# io-board-b-g.net
KiCad netlist of a schematic drawn in EAGLE
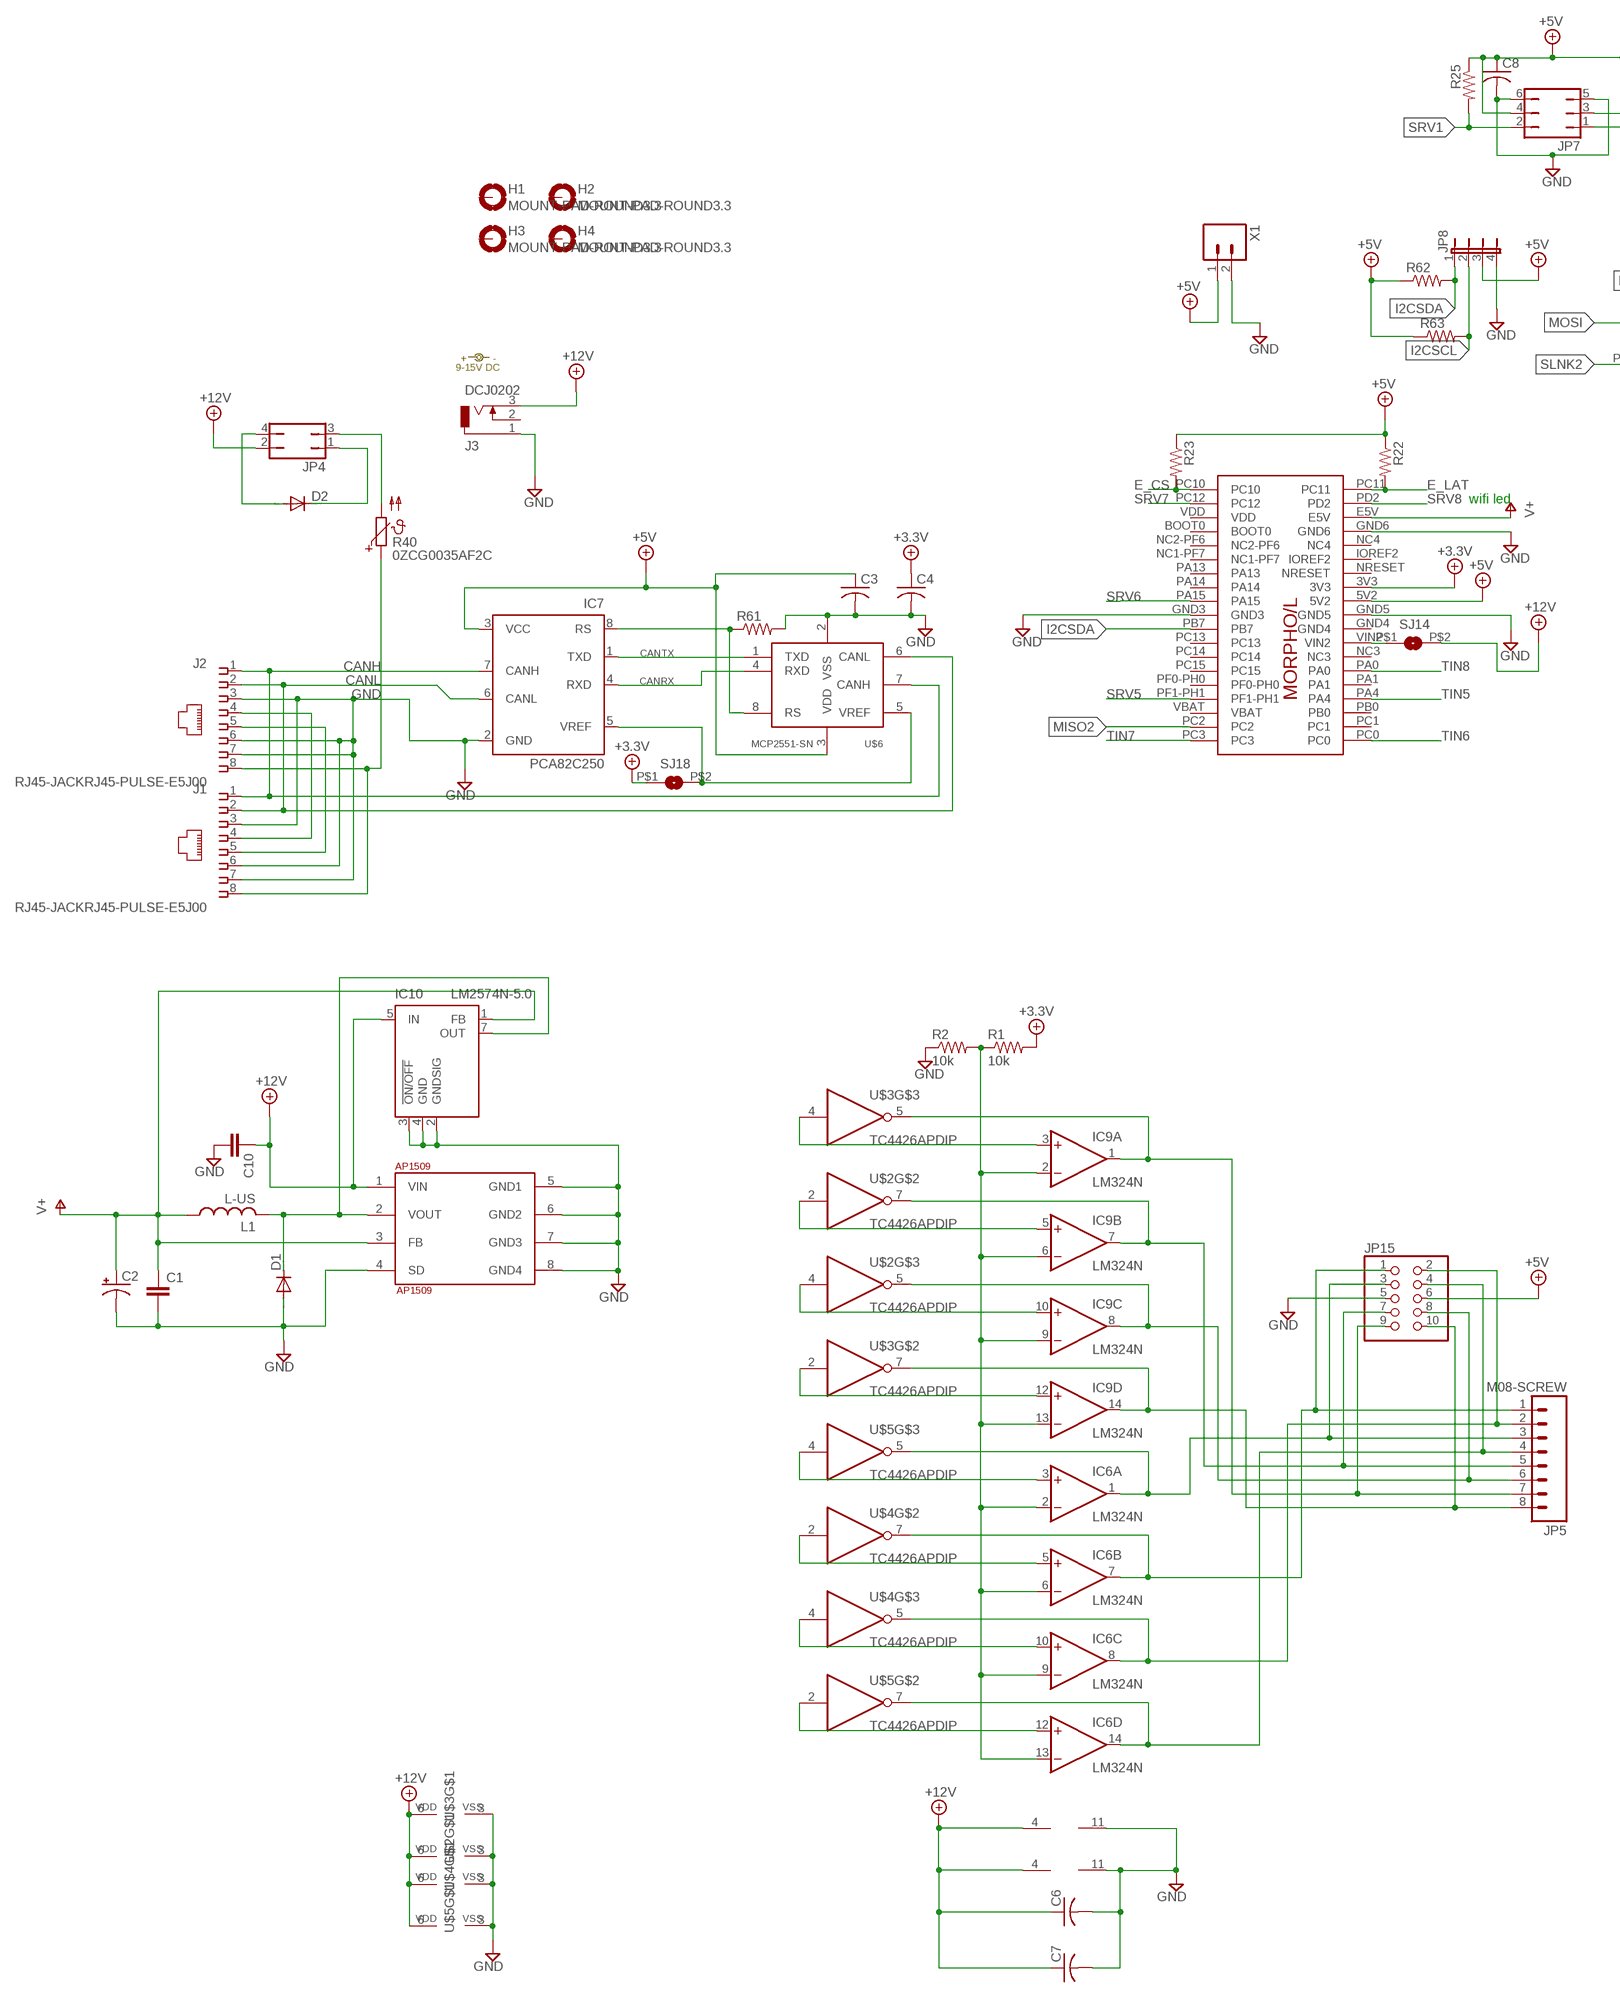
[diagram p0: schematic, sheet 1, part 1 of 2]
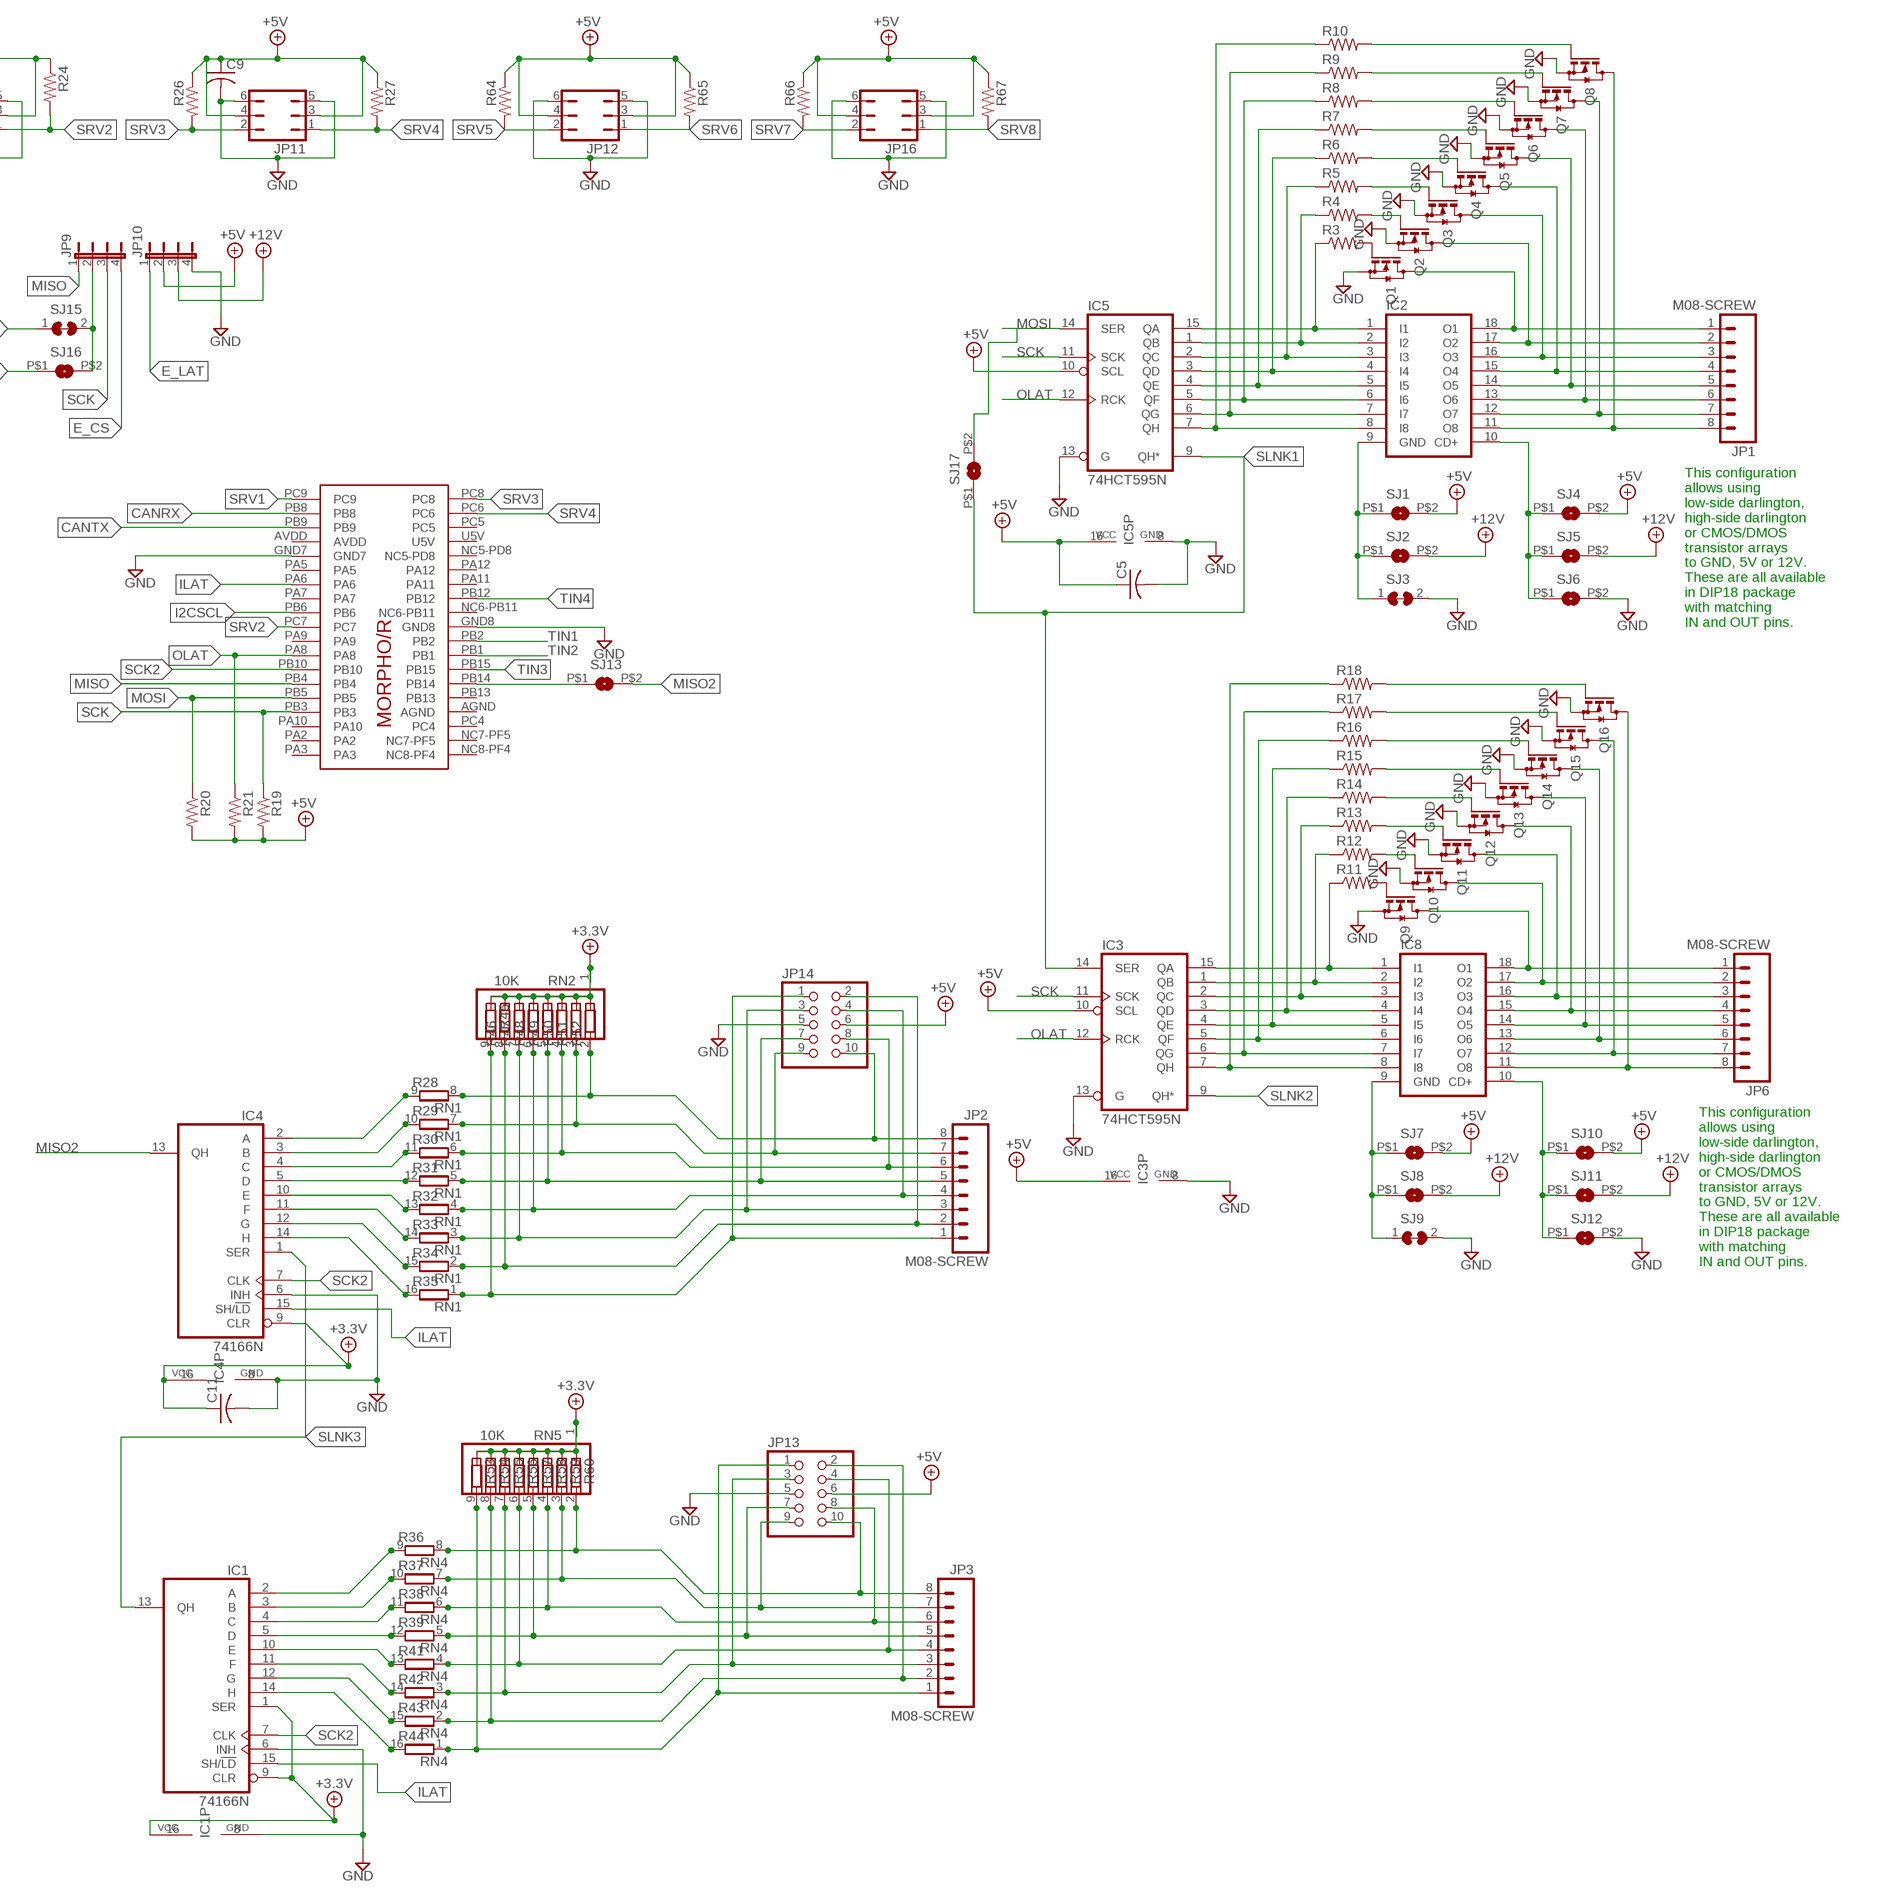
[diagram p1: schematic, sheet 1, part 2 of 2]

(export (version "E")
  (design (tool "Eeschema 10.0.6"))
  (components
    (comp (ref "+12V")
      (value "9-15V DC")
      (footprint "eagle-import:POWER_USAGE")
      (libsource (lib "eagle-import") (part "DOC-POWER_LABEL"))
    )
    (comp (ref "AP1509")
      (value "AP1509")
      (footprint "eagle-import:SO-08")
      (libsource (lib "eagle-import") (part "AP1509"))
    )
    (comp (ref "C1")
      (value "C-EUC1206")
      (footprint "eagle-import:C1206")
      (libsource (lib "eagle-import") (part "C-EUC1206"))
    )
    (comp (ref "C2")
      (value "CPOL-USE2.5-5")
      (footprint "eagle-import:E2,5-5")
      (libsource (lib "eagle-import") (part "CPOL-USE2.5-5"))
    )
    (comp (ref "C3")
      (value "C-USC0805")
      (footprint "eagle-import:C0805")
      (libsource (lib "eagle-import") (part "C-USC0805"))
    )
    (comp (ref "C4")
      (value "C-USC0805")
      (footprint "eagle-import:C0805")
      (libsource (lib "eagle-import") (part "C-USC0805"))
    )
    (comp (ref "C5")
      (value "C-USC0805")
      (footprint "eagle-import:C0805")
      (libsource (lib "eagle-import") (part "C-USC0805"))
    )
    (comp (ref "C6")
      (value "C-USC1206")
      (footprint "eagle-import:C1206")
      (libsource (lib "eagle-import") (part "C-USC1206"))
    )
    (comp (ref "C7")
      (value "C-USC1206")
      (footprint "eagle-import:C1206")
      (libsource (lib "eagle-import") (part "C-USC1206"))
    )
    (comp (ref "C8")
      (value "C-USC1206")
      (footprint "eagle-import:C1206")
      (libsource (lib "eagle-import") (part "C-USC1206"))
    )
    (comp (ref "C9")
      (value "C-USC1206")
      (footprint "eagle-import:C1206")
      (libsource (lib "eagle-import") (part "C-USC1206"))
    )
    (comp (ref "C10")
      (value "C-EUC1206")
      (footprint "eagle-import:C1206")
      (libsource (lib "eagle-import") (part "C-EUC1206"))
    )
    (comp (ref "C11")
      (value "C-USC0805")
      (footprint "eagle-import:C0805")
      (libsource (lib "eagle-import") (part "C-USC0805"))
    )
    (comp (ref "D1")
      (value "DIODE-DO41-7.6")
      (footprint "eagle-import:DO41-7.6")
      (libsource (lib "eagle-import") (part "DIODE-DO41-7.6"))
    )
    (comp (ref "D2")
      (value "DIODE-DO41-7.6")
      (footprint "eagle-import:DO41-7.6")
      (libsource (lib "eagle-import") (part "DIODE-DO41-7.6"))
    )
    (comp (ref "H1")
      (value "MOUNT-PAD-ROUND3.3")
      (footprint "eagle-import:3,3-PAD")
      (libsource (lib "eagle-import") (part "MOUNT-PAD-ROUND3.3"))
    )
    (comp (ref "H2")
      (value "MOUNT-PAD-ROUND3.3")
      (footprint "eagle-import:3,3-PAD")
      (libsource (lib "eagle-import") (part "MOUNT-PAD-ROUND3.3"))
    )
    (comp (ref "H3")
      (value "MOUNT-PAD-ROUND3.3")
      (footprint "eagle-import:3,3-PAD")
      (libsource (lib "eagle-import") (part "MOUNT-PAD-ROUND3.3"))
    )
    (comp (ref "H4")
      (value "MOUNT-PAD-ROUND3.3")
      (footprint "eagle-import:3,3-PAD")
      (libsource (lib "eagle-import") (part "MOUNT-PAD-ROUND3.3"))
    )
    (comp (ref "IC1")
      (value "74166N")
      (footprint "eagle-import:DIL16")
      (libsource (lib "eagle-import") (part "74166N"))
    )
    (comp (ref "IC2")
      (value "ULN2803A")
      (footprint "eagle-import:DIL18-THIN")
      (libsource (lib "eagle-import") (part "ULN2803A"))
    )
    (comp (ref "IC3")
      (value "74HCT595N")
      (footprint "eagle-import:DIL16")
      (libsource (lib "eagle-import") (part "74595NHCT"))
    )
    (comp (ref "IC4")
      (value "74166N")
      (footprint "eagle-import:DIL16")
      (libsource (lib "eagle-import") (part "74166N"))
    )
    (comp (ref "IC5")
      (value "74HCT595N")
      (footprint "eagle-import:DIL16")
      (libsource (lib "eagle-import") (part "74595NHCT"))
    )
    (comp (ref "IC6")
      (value "LM324N")
      (footprint "eagle-import:DIL14")
      (libsource (lib "eagle-import") (part "LM324N"))
    )
    (comp (ref "IC7")
      (value "PCA82C250")
      (footprint "eagle-import:DIL08")
      (libsource (lib "eagle-import") (part "PCA82C250"))
    )
    (comp (ref "IC8")
      (value "ULN2803A")
      (footprint "eagle-import:DIL18-THIN")
      (libsource (lib "eagle-import") (part "ULN2803A"))
    )
    (comp (ref "IC9")
      (value "LM324N")
      (footprint "eagle-import:DIL14")
      (libsource (lib "eagle-import") (part "LM324N"))
    )
    (comp (ref "IC10")
      (value "LM2574N-5.0")
      (footprint "eagle-import:DIL08")
      (libsource (lib "eagle-import") (part "LM2574?-N5.0"))
    )
    (comp (ref "J1")
      (value "RJ45-JACKRJ45-PULSE-E5J00")
      (footprint "eagle-import:RJ45-PULSE-E5J88")
      (libsource (lib "eagle-import") (part "RJ45-JACKRJ45-PULSE-E5J00"))
    )
    (comp (ref "J2")
      (value "RJ45-JACKRJ45-PULSE-E5J00")
      (footprint "eagle-import:RJ45-PULSE-E5J88")
      (libsource (lib "eagle-import") (part "RJ45-JACKRJ45-PULSE-E5J00"))
    )
    (comp (ref "J3")
      (value "DCJ0202")
      (footprint "eagle-import:DCJ0202")
      (libsource (lib "eagle-import") (part "DCJ0202"))
    )
    (comp (ref "JP1")
      (value "M08-SCREW")
      (footprint "eagle-import:1X08_TERMINAL")
      (libsource (lib "eagle-import") (part "M08-SCREW"))
    )
    (comp (ref "JP2")
      (value "M08-SCREW")
      (footprint "eagle-import:1X08_TERMINAL")
      (libsource (lib "eagle-import") (part "M08-SCREW"))
    )
    (comp (ref "JP3")
      (value "M08-SCREW")
      (footprint "eagle-import:1X08_TERMINAL")
      (libsource (lib "eagle-import") (part "M08-SCREW"))
    )
    (comp (ref "JP4")
      (value "JP2Q")
      (footprint "eagle-import:JP2Q")
      (libsource (lib "eagle-import") (part "JP2Q"))
    )
    (comp (ref "JP5")
      (value "M08-SCREW")
      (footprint "eagle-import:1X08_TERMINAL")
      (libsource (lib "eagle-import") (part "M08-SCREW"))
    )
    (comp (ref "JP6")
      (value "M08-SCREW")
      (footprint "eagle-import:1X08_TERMINAL")
      (libsource (lib "eagle-import") (part "M08-SCREW"))
    )
    (comp (ref "JP7")
      (value "JP3Q")
      (footprint "eagle-import:JP3Q")
      (libsource (lib "eagle-import") (part "JP3Q"))
    )
    (comp (ref "JP8")
      (value "JP4-FLAT")
      (footprint "eagle-import:JP4F")
      (libsource (lib "eagle-import") (part "JP4-FLAT"))
    )
    (comp (ref "JP9")
      (value "JP4-FLAT")
      (footprint "eagle-import:JP4F")
      (libsource (lib "eagle-import") (part "JP4-FLAT"))
    )
    (comp (ref "JP10")
      (value "JP4-FLAT")
      (footprint "eagle-import:JP4F")
      (libsource (lib "eagle-import") (part "JP4-FLAT"))
    )
    (comp (ref "JP11")
      (value "JP3Q")
      (footprint "eagle-import:JP3Q")
      (libsource (lib "eagle-import") (part "JP3Q"))
    )
    (comp (ref "JP12")
      (value "JP3Q")
      (footprint "eagle-import:JP3Q")
      (libsource (lib "eagle-import") (part "JP3Q"))
    )
    (comp (ref "JP13")
      (value "PINHD-2X5CN")
      (footprint "eagle-import:CON10M")
      (libsource (lib "eagle-import") (part "PINHD-2X5CN"))
    )
    (comp (ref "JP14")
      (value "PINHD-2X5CN")
      (footprint "eagle-import:CON10M")
      (libsource (lib "eagle-import") (part "PINHD-2X5CN"))
    )
    (comp (ref "JP15")
      (value "PINHD-2X5CN")
      (footprint "eagle-import:CON10M")
      (libsource (lib "eagle-import") (part "PINHD-2X5CN"))
    )
    (comp (ref "JP16")
      (value "JP3Q")
      (footprint "eagle-import:JP3Q")
      (libsource (lib "eagle-import") (part "JP3Q"))
    )
    (comp (ref "L1")
      (value "L-US")
      (footprint "eagle-import:L5-8,5")
      (libsource (lib "eagle-import") (part "L-US"))
    )
    (comp (ref "Q1")
      (value "BSS123")
      (footprint "eagle-import:SOT23")
      (libsource (lib "eagle-import") (part "BSS123"))
    )
    (comp (ref "Q2")
      (value "BSS123")
      (footprint "eagle-import:SOT23")
      (libsource (lib "eagle-import") (part "BSS123"))
    )
    (comp (ref "Q3")
      (value "BSS123")
      (footprint "eagle-import:SOT23")
      (libsource (lib "eagle-import") (part "BSS123"))
    )
    (comp (ref "Q4")
      (value "BSS123")
      (footprint "eagle-import:SOT23")
      (libsource (lib "eagle-import") (part "BSS123"))
    )
    (comp (ref "Q5")
      (value "BSS123")
      (footprint "eagle-import:SOT23")
      (libsource (lib "eagle-import") (part "BSS123"))
    )
    (comp (ref "Q6")
      (value "BSS123")
      (footprint "eagle-import:SOT23")
      (libsource (lib "eagle-import") (part "BSS123"))
    )
    (comp (ref "Q7")
      (value "BSS123")
      (footprint "eagle-import:SOT23")
      (libsource (lib "eagle-import") (part "BSS123"))
    )
    (comp (ref "Q8")
      (value "BSS123")
      (footprint "eagle-import:SOT23")
      (libsource (lib "eagle-import") (part "BSS123"))
    )
    (comp (ref "Q9")
      (value "BSS123")
      (footprint "eagle-import:SOT23")
      (libsource (lib "eagle-import") (part "BSS123"))
    )
    (comp (ref "Q10")
      (value "BSS123")
      (footprint "eagle-import:SOT23")
      (libsource (lib "eagle-import") (part "BSS123"))
    )
    (comp (ref "Q11")
      (value "BSS123")
      (footprint "eagle-import:SOT23")
      (libsource (lib "eagle-import") (part "BSS123"))
    )
    (comp (ref "Q12")
      (value "BSS123")
      (footprint "eagle-import:SOT23")
      (libsource (lib "eagle-import") (part "BSS123"))
    )
    (comp (ref "Q13")
      (value "BSS123")
      (footprint "eagle-import:SOT23")
      (libsource (lib "eagle-import") (part "BSS123"))
    )
    (comp (ref "Q14")
      (value "BSS123")
      (footprint "eagle-import:SOT23")
      (libsource (lib "eagle-import") (part "BSS123"))
    )
    (comp (ref "Q15")
      (value "BSS123")
      (footprint "eagle-import:SOT23")
      (libsource (lib "eagle-import") (part "BSS123"))
    )
    (comp (ref "Q16")
      (value "BSS123")
      (footprint "eagle-import:SOT23")
      (libsource (lib "eagle-import") (part "BSS123"))
    )
    (comp (ref "R1")
      (value "10k")
      (footprint "eagle-import:R0805")
      (libsource (lib "eagle-import") (part "R-US_R0805"))
    )
    (comp (ref "R2")
      (value "10k")
      (footprint "eagle-import:R0805")
      (libsource (lib "eagle-import") (part "R-US_R0805"))
    )
    (comp (ref "R3")
      (value "R-US_R0603")
      (footprint "eagle-import:R0603")
      (libsource (lib "eagle-import") (part "R-US_R0603"))
    )
    (comp (ref "R4")
      (value "R-US_R0603")
      (footprint "eagle-import:R0603")
      (libsource (lib "eagle-import") (part "R-US_R0603"))
    )
    (comp (ref "R5")
      (value "R-US_R0603")
      (footprint "eagle-import:R0603")
      (libsource (lib "eagle-import") (part "R-US_R0603"))
    )
    (comp (ref "R6")
      (value "R-US_R0603")
      (footprint "eagle-import:R0603")
      (libsource (lib "eagle-import") (part "R-US_R0603"))
    )
    (comp (ref "R7")
      (value "R-US_R0603")
      (footprint "eagle-import:R0603")
      (libsource (lib "eagle-import") (part "R-US_R0603"))
    )
    (comp (ref "R8")
      (value "R-US_R0603")
      (footprint "eagle-import:R0603")
      (libsource (lib "eagle-import") (part "R-US_R0603"))
    )
    (comp (ref "R9")
      (value "R-US_R0603")
      (footprint "eagle-import:R0603")
      (libsource (lib "eagle-import") (part "R-US_R0603"))
    )
    (comp (ref "R10")
      (value "R-US_R0603")
      (footprint "eagle-import:R0603")
      (libsource (lib "eagle-import") (part "R-US_R0603"))
    )
    (comp (ref "R11")
      (value "R-US_R0603")
      (footprint "eagle-import:R0603")
      (libsource (lib "eagle-import") (part "R-US_R0603"))
    )
    (comp (ref "R12")
      (value "R-US_R0603")
      (footprint "eagle-import:R0603")
      (libsource (lib "eagle-import") (part "R-US_R0603"))
    )
    (comp (ref "R13")
      (value "R-US_R0603")
      (footprint "eagle-import:R0603")
      (libsource (lib "eagle-import") (part "R-US_R0603"))
    )
    (comp (ref "R14")
      (value "R-US_R0603")
      (footprint "eagle-import:R0603")
      (libsource (lib "eagle-import") (part "R-US_R0603"))
    )
    (comp (ref "R15")
      (value "R-US_R0603")
      (footprint "eagle-import:R0603")
      (libsource (lib "eagle-import") (part "R-US_R0603"))
    )
    (comp (ref "R16")
      (value "R-US_R0603")
      (footprint "eagle-import:R0603")
      (libsource (lib "eagle-import") (part "R-US_R0603"))
    )
    (comp (ref "R17")
      (value "R-US_R0603")
      (footprint "eagle-import:R0603")
      (libsource (lib "eagle-import") (part "R-US_R0603"))
    )
    (comp (ref "R18")
      (value "R-US_R0603")
      (footprint "eagle-import:R0603")
      (libsource (lib "eagle-import") (part "R-US_R0603"))
    )
    (comp (ref "R19")
      (value "R-US_R0805")
      (footprint "eagle-import:R0805")
      (libsource (lib "eagle-import") (part "rcl_334_R-US_R0805"))
    )
    (comp (ref "R20")
      (value "R-US_R0805")
      (footprint "eagle-import:R0805")
      (libsource (lib "eagle-import") (part "rcl_334_R-US_R0805"))
    )
    (comp (ref "R21")
      (value "R-US_R0805")
      (footprint "eagle-import:R0805")
      (libsource (lib "eagle-import") (part "rcl_334_R-US_R0805"))
    )
    (comp (ref "R22")
      (value "R-US_R0805")
      (footprint "eagle-import:R0805")
      (libsource (lib "eagle-import") (part "rcl_334_R-US_R0805"))
    )
    (comp (ref "R23")
      (value "R-US_R0805")
      (footprint "eagle-import:R0805")
      (libsource (lib "eagle-import") (part "rcl_334_R-US_R0805"))
    )
    (comp (ref "R24")
      (value "R-US_R0805")
      (footprint "eagle-import:R0805")
      (libsource (lib "eagle-import") (part "rcl_334_R-US_R0805"))
    )
    (comp (ref "R25")
      (value "R-US_R0805")
      (footprint "eagle-import:R0805")
      (libsource (lib "eagle-import") (part "rcl_334_R-US_R0805"))
    )
    (comp (ref "R26")
      (value "R-US_R0805")
      (footprint "eagle-import:R0805")
      (libsource (lib "eagle-import") (part "rcl_334_R-US_R0805"))
    )
    (comp (ref "R27")
      (value "R-US_R0805")
      (footprint "eagle-import:R0805")
      (libsource (lib "eagle-import") (part "rcl_334_R-US_R0805"))
    )
    (comp (ref "R28")
      (value "R-EU_R0603")
      (footprint "eagle-import:R0603")
      (libsource (lib "eagle-import") (part "R-EU_R0603"))
    )
    (comp (ref "R29")
      (value "R-EU_R0603")
      (footprint "eagle-import:R0603")
      (libsource (lib "eagle-import") (part "R-EU_R0603"))
    )
    (comp (ref "R30")
      (value "R-EU_R0603")
      (footprint "eagle-import:R0603")
      (libsource (lib "eagle-import") (part "R-EU_R0603"))
    )
    (comp (ref "R31")
      (value "R-EU_R0603")
      (footprint "eagle-import:R0603")
      (libsource (lib "eagle-import") (part "R-EU_R0603"))
    )
    (comp (ref "R32")
      (value "R-EU_R0603")
      (footprint "eagle-import:R0603")
      (libsource (lib "eagle-import") (part "R-EU_R0603"))
    )
    (comp (ref "R33")
      (value "R-EU_R0603")
      (footprint "eagle-import:R0603")
      (libsource (lib "eagle-import") (part "R-EU_R0603"))
    )
    (comp (ref "R34")
      (value "R-EU_R0603")
      (footprint "eagle-import:R0603")
      (libsource (lib "eagle-import") (part "R-EU_R0603"))
    )
    (comp (ref "R35")
      (value "R-EU_R0603")
      (footprint "eagle-import:R0603")
      (libsource (lib "eagle-import") (part "R-EU_R0603"))
    )
    (comp (ref "R36")
      (value "R-EU_R0603")
      (footprint "eagle-import:R0603")
      (libsource (lib "eagle-import") (part "R-EU_R0603"))
    )
    (comp (ref "R37")
      (value "R-EU_R0603")
      (footprint "eagle-import:R0603")
      (libsource (lib "eagle-import") (part "R-EU_R0603"))
    )
    (comp (ref "R38")
      (value "R-EU_R0603")
      (footprint "eagle-import:R0603")
      (libsource (lib "eagle-import") (part "R-EU_R0603"))
    )
    (comp (ref "R39")
      (value "R-EU_R0603")
      (footprint "eagle-import:R0603")
      (libsource (lib "eagle-import") (part "R-EU_R0603"))
    )
    (comp (ref "R40")
      (value "0ZCG0035AF2C")
      (footprint "eagle-import:PTC1812")
      (libsource (lib "eagle-import") (part "PTC_1812"))
    )
    (comp (ref "R41")
      (value "R-EU_R0603")
      (footprint "eagle-import:R0603")
      (libsource (lib "eagle-import") (part "R-EU_R0603"))
    )
    (comp (ref "R42")
      (value "R-EU_R0603")
      (footprint "eagle-import:R0603")
      (libsource (lib "eagle-import") (part "R-EU_R0603"))
    )
    (comp (ref "R43")
      (value "R-EU_R0603")
      (footprint "eagle-import:R0603")
      (libsource (lib "eagle-import") (part "R-EU_R0603"))
    )
    (comp (ref "R44")
      (value "R-EU_R0603")
      (footprint "eagle-import:R0603")
      (libsource (lib "eagle-import") (part "R-EU_R0603"))
    )
    (comp (ref "R45")
      (value "R-EU_R0603")
      (footprint "eagle-import:R0603")
      (libsource (lib "eagle-import") (part "R-EU_R0603"))
    )
    (comp (ref "R46")
      (value "R-EU_R0603")
      (footprint "eagle-import:R0603")
      (libsource (lib "eagle-import") (part "R-EU_R0603"))
    )
    (comp (ref "R47")
      (value "R-EU_R0603")
      (footprint "eagle-import:R0603")
      (libsource (lib "eagle-import") (part "R-EU_R0603"))
    )
    (comp (ref "R48")
      (value "R-EU_R0603")
      (footprint "eagle-import:R0603")
      (libsource (lib "eagle-import") (part "R-EU_R0603"))
    )
    (comp (ref "R49")
      (value "R-EU_R0603")
      (footprint "eagle-import:R0603")
      (libsource (lib "eagle-import") (part "R-EU_R0603"))
    )
    (comp (ref "R50")
      (value "R-EU_R0603")
      (footprint "eagle-import:R0603")
      (libsource (lib "eagle-import") (part "R-EU_R0603"))
    )
    (comp (ref "R51")
      (value "R-EU_R0603")
      (footprint "eagle-import:R0603")
      (libsource (lib "eagle-import") (part "R-EU_R0603"))
    )
    (comp (ref "R52")
      (value "R-EU_R0603")
      (footprint "eagle-import:R0603")
      (libsource (lib "eagle-import") (part "R-EU_R0603"))
    )
    (comp (ref "R53")
      (value "R-EU_R0603")
      (footprint "eagle-import:R0603")
      (libsource (lib "eagle-import") (part "R-EU_R0603"))
    )
    (comp (ref "R54")
      (value "R-EU_R0603")
      (footprint "eagle-import:R0603")
      (libsource (lib "eagle-import") (part "R-EU_R0603"))
    )
    (comp (ref "R55")
      (value "R-EU_R0603")
      (footprint "eagle-import:R0603")
      (libsource (lib "eagle-import") (part "R-EU_R0603"))
    )
    (comp (ref "R56")
      (value "R-EU_R0603")
      (footprint "eagle-import:R0603")
      (libsource (lib "eagle-import") (part "R-EU_R0603"))
    )
    (comp (ref "R57")
      (value "R-EU_R0603")
      (footprint "eagle-import:R0603")
      (libsource (lib "eagle-import") (part "R-EU_R0603"))
    )
    (comp (ref "R58")
      (value "R-EU_R0603")
      (footprint "eagle-import:R0603")
      (libsource (lib "eagle-import") (part "R-EU_R0603"))
    )
    (comp (ref "R59")
      (value "R-EU_R0603")
      (footprint "eagle-import:R0603")
      (libsource (lib "eagle-import") (part "R-EU_R0603"))
    )
    (comp (ref "R60")
      (value "R-EU_R0603")
      (footprint "eagle-import:R0603")
      (libsource (lib "eagle-import") (part "R-EU_R0603"))
    )
    (comp (ref "R61")
      (value "R-US_R0805")
      (footprint "eagle-import:R0805")
      (libsource (lib "eagle-import") (part "rcl_334_R-US_R0805"))
    )
    (comp (ref "R62")
      (value "R-US_R0805")
      (footprint "eagle-import:R0805")
      (libsource (lib "eagle-import") (part "rcl_334_R-US_R0805"))
    )
    (comp (ref "R63")
      (value "R-US_R0805")
      (footprint "eagle-import:R0805")
      (libsource (lib "eagle-import") (part "rcl_334_R-US_R0805"))
    )
    (comp (ref "R64")
      (value "R-US_R0805")
      (footprint "eagle-import:R0805")
      (libsource (lib "eagle-import") (part "rcl_334_R-US_R0805"))
    )
    (comp (ref "R65")
      (value "R-US_R0805")
      (footprint "eagle-import:R0805")
      (libsource (lib "eagle-import") (part "rcl_334_R-US_R0805"))
    )
    (comp (ref "R66")
      (value "R-US_R0805")
      (footprint "eagle-import:R0805")
      (libsource (lib "eagle-import") (part "rcl_334_R-US_R0805"))
    )
    (comp (ref "R67")
      (value "R-US_R0805")
      (footprint "eagle-import:R0805")
      (libsource (lib "eagle-import") (part "rcl_334_R-US_R0805"))
    )
    (comp (ref "RN1")
      (value "8R-P")
      (footprint "eagle-import:DIL16")
      (libsource (lib "eagle-import") (part "8R-P"))
    )
    (comp (ref "RN2")
      (value "10K")
      (footprint "eagle-import:SIL9")
      (libsource (lib "eagle-import") (part "G08R"))
    )
    (comp (ref "RN4")
      (value "8R-P")
      (footprint "eagle-import:DIL16")
      (libsource (lib "eagle-import") (part "8R-P"))
    )
    (comp (ref "RN5")
      (value "10K")
      (footprint "eagle-import:SIL9")
      (libsource (lib "eagle-import") (part "G08R"))
    )
    (comp (ref "SJ1")
      (value "SJRND2")
      (footprint "eagle-import:SJ_RND2")
      (libsource (lib "eagle-import") (part "SJRND2"))
    )
    (comp (ref "SJ2")
      (value "SJRND2")
      (footprint "eagle-import:SJ_RND2")
      (libsource (lib "eagle-import") (part "SJRND2"))
    )
    (comp (ref "SJ3")
      (value "SJ-C")
      (footprint "eagle-import:SJW-C")
      (libsource (lib "eagle-import") (part "SJ-C"))
    )
    (comp (ref "SJ4")
      (value "SJRND2")
      (footprint "eagle-import:SJ_RND2")
      (libsource (lib "eagle-import") (part "SJRND2"))
    )
    (comp (ref "SJ5")
      (value "SJRND2")
      (footprint "eagle-import:SJ_RND2")
      (libsource (lib "eagle-import") (part "SJRND2"))
    )
    (comp (ref "SJ6")
      (value "SJRND2")
      (footprint "eagle-import:SJ_RND2")
      (libsource (lib "eagle-import") (part "SJRND2"))
    )
    (comp (ref "SJ7")
      (value "SJRND2")
      (footprint "eagle-import:SJ_RND2")
      (libsource (lib "eagle-import") (part "SJRND2"))
    )
    (comp (ref "SJ8")
      (value "SJRND2")
      (footprint "eagle-import:SJ_RND2")
      (libsource (lib "eagle-import") (part "SJRND2"))
    )
    (comp (ref "SJ9")
      (value "SJ-C")
      (footprint "eagle-import:SJW-C")
      (libsource (lib "eagle-import") (part "SJ-C"))
    )
    (comp (ref "SJ10")
      (value "SJRND2")
      (footprint "eagle-import:SJ_RND2")
      (libsource (lib "eagle-import") (part "SJRND2"))
    )
    (comp (ref "SJ11")
      (value "SJRND2")
      (footprint "eagle-import:SJ_RND2")
      (libsource (lib "eagle-import") (part "SJRND2"))
    )
    (comp (ref "SJ12")
      (value "SJRND2")
      (footprint "eagle-import:SJ_RND2")
      (libsource (lib "eagle-import") (part "SJRND2"))
    )
    (comp (ref "SJ13")
      (value "SJRND2")
      (footprint "eagle-import:SJ_RND2")
      (libsource (lib "eagle-import") (part "SJRND2"))
    )
    (comp (ref "SJ14")
      (value "SJRND2")
      (footprint "eagle-import:SJ_RND2")
      (libsource (lib "eagle-import") (part "SJRND2"))
    )
    (comp (ref "SJ15")
      (value "SJ-C")
      (footprint "eagle-import:SJW-C")
      (libsource (lib "eagle-import") (part "SJ-C"))
    )
    (comp (ref "SJ16")
      (value "SJRND2")
      (footprint "eagle-import:SJ_RND2")
      (libsource (lib "eagle-import") (part "SJRND2"))
    )
    (comp (ref "SJ17")
      (value "SJRND2")
      (footprint "eagle-import:SJ_RND2")
      (libsource (lib "eagle-import") (part "SJRND2"))
    )
    (comp (ref "SJ18")
      (value "SJRND2")
      (footprint "eagle-import:SJ_RND2")
      (libsource (lib "eagle-import") (part "SJRND2"))
    )
    (comp (ref "U$1")
      (value "NUCLEO_64_GENERIC")
      (footprint "eagle-import:NUCLEO_BRD_BASE64")
      (libsource (lib "eagle-import") (part "NUCLEO_64_GENERIC"))
    )
    (comp (ref "U$2")
      (value "TC4426APDIP")
      (footprint "eagle-import:DIL08-LONG")
      (libsource (lib "eagle-import") (part "TC4426APDIP"))
    )
    (comp (ref "U$3")
      (value "TC4426APDIP")
      (footprint "eagle-import:DIL08-LONG")
      (libsource (lib "eagle-import") (part "TC4426APDIP"))
    )
    (comp (ref "U$4")
      (value "TC4426APDIP")
      (footprint "eagle-import:DIL08-LONG")
      (libsource (lib "eagle-import") (part "TC4426APDIP"))
    )
    (comp (ref "U$5")
      (value "TC4426APDIP")
      (footprint "eagle-import:DIL08-LONG")
      (libsource (lib "eagle-import") (part "TC4426APDIP"))
    )
    (comp (ref "U$6")
      (value "MCP2551-SN")
      (footprint "eagle-import:SO-08")
      (libsource (lib "eagle-import") (part "MCP2551-SN"))
    )
    (comp (ref "X1")
      (value "CONNECTOR-M023.5MM-LOCK")
      (footprint "eagle-import:SCREWTERMINAL-3.5MM-2_LOCK")
      (libsource (lib "eagle-import") (part "CONNECTOR-M023.5MM-LOCK"))
    )
  )
  (nets
    (net (code "1") (name "+3.3V") (class "Default")
      (node (ref "C11") (pin "1") (pinfunction "1_1") (pintype "passive"))
      (node (ref "C4") (pin "1") (pinfunction "1_1") (pintype "passive"))
      (node (ref "IC1") (pin "1") (pinfunction "SER_1") (pintype "input"))
      (node (ref "IC1") (pin "16") (pinfunction "VCC_16") (pintype "power_in"))
      (node (ref "IC1") (pin "9") (pinfunction "CLR_9") (pintype "input"))
      (node (ref "IC4") (pin "16") (pinfunction "VCC_16") (pintype "power_in"))
      (node (ref "IC4") (pin "9") (pinfunction "CLR_9") (pintype "input"))
      (node (ref "R1") (pin "2") (pinfunction "2_2") (pintype "passive"))
      (node (ref "R45") (pin "1") (pinfunction "1_1") (pintype "passive"))
      (node (ref "R46") (pin "2") (pinfunction "2_2") (pintype "passive"))
      (node (ref "R47") (pin "2") (pinfunction "2_2") (pintype "passive"))
      (node (ref "R48") (pin "2") (pinfunction "2_2") (pintype "passive"))
      (node (ref "R49") (pin "2") (pinfunction "2_2") (pintype "passive"))
      (node (ref "R50") (pin "2") (pinfunction "2_2") (pintype "passive"))
      (node (ref "R51") (pin "2") (pinfunction "2_2") (pintype "passive"))
      (node (ref "R52") (pin "2") (pinfunction "2_2") (pintype "passive"))
      (node (ref "R53") (pin "1") (pinfunction "1_1") (pintype "passive"))
      (node (ref "R54") (pin "1") (pinfunction "1_1") (pintype "passive"))
      (node (ref "R55") (pin "1") (pinfunction "1_1") (pintype "passive"))
      (node (ref "R56") (pin "1") (pinfunction "1_1") (pintype "passive"))
      (node (ref "R57") (pin "1") (pinfunction "1_1") (pintype "passive"))
      (node (ref "R58") (pin "1") (pinfunction "1_1") (pintype "passive"))
      (node (ref "R59") (pin "1") (pinfunction "1_1") (pintype "passive"))
      (node (ref "R60") (pin "1") (pinfunction "1_1") (pintype "passive"))
      (node (ref "RN2") (pin "1") (pinfunction "1_1") (pintype "passive"))
      (node (ref "RN5") (pin "1") (pinfunction "1_1") (pintype "passive"))
      (node (ref "SJ18") (pin "P$1") (pinfunction "1_P$1") (pintype "passive"))
      (node (ref "U$1") (pin "3V3") (pinfunction "3V3_3V3") (pintype "power_in"))
    )
    (net (code "2") (name "+5V") (class "Default")
      (node (ref "C3") (pin "1") (pinfunction "1_1") (pintype "passive"))
      (node (ref "C5") (pin "1") (pinfunction "1_1") (pintype "passive"))
      (node (ref "C8") (pin "1") (pinfunction "1_1") (pintype "passive"))
      (node (ref "C9") (pin "1") (pinfunction "1_1") (pintype "passive"))
      (node (ref "IC3") (pin "10") (pinfunction "SCL_10") (pintype "input"))
      (node (ref "IC3") (pin "16") (pinfunction "VCC_16") (pintype "power_in"))
      (node (ref "IC5") (pin "10") (pinfunction "SCL_10") (pintype "input"))
      (node (ref "IC5") (pin "16") (pinfunction "VCC_16") (pintype "power_in"))
      (node (ref "IC7") (pin "3") (pinfunction "VCC_3") (pintype "power_in"))
      (node (ref "JP10") (pin "2") (pinfunction "2_2") (pintype "passive"))
      (node (ref "JP11") (pin "3") (pinfunction "3_3") (pintype "passive"))
      (node (ref "JP11") (pin "4") (pinfunction "4_4") (pintype "passive"))
      (node (ref "JP12") (pin "3") (pinfunction "3_3") (pintype "passive"))
      (node (ref "JP12") (pin "4") (pinfunction "4_4") (pintype "passive"))
      (node (ref "JP13") (pin "6") (pinfunction "6_6") (pintype "passive"))
      (node (ref "JP14") (pin "6") (pinfunction "6_6") (pintype "passive"))
      (node (ref "JP15") (pin "6") (pinfunction "6_6") (pintype "passive"))
      (node (ref "JP16") (pin "3") (pinfunction "3_3") (pintype "passive"))
      (node (ref "JP16") (pin "4") (pinfunction "4_4") (pintype "passive"))
      (node (ref "JP7") (pin "3") (pinfunction "3_3") (pintype "passive"))
      (node (ref "JP7") (pin "4") (pinfunction "4_4") (pintype "passive"))
      (node (ref "JP8") (pin "3") (pinfunction "3_3") (pintype "passive"))
      (node (ref "R19") (pin "2") (pinfunction "2_2") (pintype "passive"))
      (node (ref "R20") (pin "2") (pinfunction "2_2") (pintype "passive"))
      (node (ref "R21") (pin "2") (pinfunction "2_2") (pintype "passive"))
      (node (ref "R22") (pin "1") (pinfunction "1_1") (pintype "passive"))
      (node (ref "R23") (pin "1") (pinfunction "1_1") (pintype "passive"))
      (node (ref "R24") (pin "1") (pinfunction "1_1") (pintype "passive"))
      (node (ref "R25") (pin "1") (pinfunction "1_1") (pintype "passive"))
      (node (ref "R26") (pin "1") (pinfunction "1_1") (pintype "passive"))
      (node (ref "R27") (pin "1") (pinfunction "1_1") (pintype "passive"))
      (node (ref "R62") (pin "1") (pinfunction "1_1") (pintype "passive"))
      (node (ref "R63") (pin "1") (pinfunction "1_1") (pintype "passive"))
      (node (ref "R64") (pin "1") (pinfunction "1_1") (pintype "passive"))
      (node (ref "R65") (pin "1") (pinfunction "1_1") (pintype "passive"))
      (node (ref "R66") (pin "1") (pinfunction "1_1") (pintype "passive"))
      (node (ref "R67") (pin "1") (pinfunction "1_1") (pintype "passive"))
      (node (ref "SJ1") (pin "P$2") (pinfunction "2_P$2") (pintype "passive"))
      (node (ref "SJ10") (pin "P$2") (pinfunction "2_P$2") (pintype "passive"))
      (node (ref "SJ4") (pin "P$2") (pinfunction "2_P$2") (pintype "passive"))
      (node (ref "SJ7") (pin "P$2") (pinfunction "2_P$2") (pintype "passive"))
      (node (ref "U$1") (pin "5V2") (pinfunction "5V2_5V2") (pintype "power_in"))
      (node (ref "U$6") (pin "3") (pinfunction "VDD_3") (pintype "power_in"))
      (node (ref "X1") (pin "1") (pinfunction "1_1") (pintype "passive"))
    )
    (net (code "3") (name "+12V") (class "Default")
      (node (ref "AP1509") (pin "1") (pinfunction "VIN_1") (pintype "bidirectional"))
      (node (ref "C10") (pin "1") (pinfunction "1_1") (pintype "passive"))
      (node (ref "C6") (pin "1") (pinfunction "1_1") (pintype "passive"))
      (node (ref "C7") (pin "1") (pinfunction "1_1") (pintype "passive"))
      (node (ref "IC10") (pin "5") (pinfunction "IN_5") (pintype "input"))
      (node (ref "IC6") (pin "4") (pinfunction "V+_4") (pintype "power_in"))
      (node (ref "IC9") (pin "4") (pinfunction "V+_4") (pintype "power_in"))
      (node (ref "J3") (pin "3") (pinfunction "3_3") (pintype "passive"))
      (node (ref "JP10") (pin "3") (pinfunction "3_3") (pintype "passive"))
      (node (ref "JP4") (pin "2") (pinfunction "2_2") (pintype "passive"))
      (node (ref "SJ11") (pin "P$2") (pinfunction "2_P$2") (pintype "passive"))
      (node (ref "SJ14") (pin "P$2") (pinfunction "2_P$2") (pintype "passive"))
      (node (ref "SJ2") (pin "P$2") (pinfunction "2_P$2") (pintype "passive"))
      (node (ref "SJ5") (pin "P$2") (pinfunction "2_P$2") (pintype "passive"))
      (node (ref "SJ8") (pin "P$2") (pinfunction "2_P$2") (pintype "passive"))
      (node (ref "U$2") (pin "6") (pinfunction "VDD_6") (pintype "power_in"))
      (node (ref "U$3") (pin "6") (pinfunction "VDD_6") (pintype "power_in"))
      (node (ref "U$4") (pin "6") (pinfunction "VDD_6") (pintype "power_in"))
      (node (ref "U$5") (pin "6") (pinfunction "VDD_6") (pintype "power_in"))
    )
    (net (code "4") (name "/AGND") (class "Default")
      (node (ref "U$1") (pin "AGND") (pinfunction "AGND_AGND") (pintype "power_in"))
    )
    (net (code "5") (name "/AVDD") (class "Default")
      (node (ref "U$1") (pin "AVDD") (pinfunction "AVDD_AVDD") (pintype "power_in"))
    )
    (net (code "6") (name "/CANH") (class "Default")
      (node (ref "IC7") (pin "7") (pinfunction "CANH_7") (pintype "bidirectional"))
      (node (ref "J1") (pin "1") (pinfunction "1_1") (pintype "passive"))
      (node (ref "J2") (pin "1") (pinfunction "1_1") (pintype "passive"))
      (node (ref "U$6") (pin "7") (pinfunction "CANH_7") (pintype "bidirectional"))
    )
    (net (code "7") (name "/CANL") (class "Default")
      (node (ref "IC7") (pin "6") (pinfunction "CANL_6") (pintype "bidirectional"))
      (node (ref "J1") (pin "2") (pinfunction "2_2") (pintype "passive"))
      (node (ref "J2") (pin "2") (pinfunction "2_2") (pintype "passive"))
      (node (ref "U$6") (pin "6") (pinfunction "CANL_6") (pintype "bidirectional"))
    )
    (net (code "8") (name "/GND4") (class "Default")
      (node (ref "U$1") (pin "GND4") (pinfunction "GND4_GND4") (pintype "power_in"))
    )
    (net (code "9") (name "/TIN1") (class "Default")
      (node (ref "IC9") (pin "3") (pinfunction "+IN_3") (pintype "input"))
      (node (ref "U$1") (pin "PB2") (pinfunction "PB2_PB2") (pintype "bidirectional"))
      (node (ref "U$3") (pin "4") (pinfunction "I_4") (pintype "input"))
    )
    (net (code "10") (name "/TIN2") (class "Default")
      (node (ref "IC9") (pin "5") (pinfunction "+IN_5") (pintype "input"))
      (node (ref "U$1") (pin "PB1") (pinfunction "PB1_PB1") (pintype "bidirectional"))
      (node (ref "U$2") (pin "2") (pinfunction "I_2") (pintype "input"))
    )
    (net (code "11") (name "/TIN5") (class "Default")
      (node (ref "IC6") (pin "3") (pinfunction "+IN_3") (pintype "input"))
      (node (ref "U$1") (pin "PA4") (pinfunction "PA4_PA4") (pintype "bidirectional"))
      (node (ref "U$5") (pin "4") (pinfunction "I_4") (pintype "input"))
    )
    (net (code "12") (name "/TIN6") (class "Default")
      (node (ref "IC6") (pin "5") (pinfunction "+IN_5") (pintype "input"))
      (node (ref "U$1") (pin "PC0") (pinfunction "PC0_PC0") (pintype "bidirectional"))
      (node (ref "U$4") (pin "2") (pinfunction "I_2") (pintype "input"))
    )
    (net (code "13") (name "/TIN7") (class "Default")
      (node (ref "IC6") (pin "10") (pinfunction "+IN_10") (pintype "input"))
      (node (ref "U$1") (pin "PC3") (pinfunction "PC3_PC3") (pintype "bidirectional"))
      (node (ref "U$4") (pin "4") (pinfunction "I_4") (pintype "input"))
    )
    (net (code "14") (name "/TIN8") (class "Default")
      (node (ref "IC6") (pin "12") (pinfunction "+IN_12") (pintype "input"))
      (node (ref "U$1") (pin "PA0") (pinfunction "PA0_PA0") (pintype "bidirectional"))
      (node (ref "U$5") (pin "2") (pinfunction "I_2") (pintype "input"))
    )
    (net (code "15") (name "/U5V") (class "Default")
      (node (ref "U$1") (pin "U5V") (pinfunction "U5V_U5V") (pintype "power_in"))
    )
    (net (code "16") (name "/VBAT") (class "Default")
      (node (ref "U$1") (pin "VBAT") (pinfunction "VBAT_VBAT") (pintype "power_in"))
    )
    (net (code "17") (name "/VDD") (class "Default")
      (node (ref "U$1") (pin "VDD") (pinfunction "VDD_VDD") (pintype "power_in"))
    )
    (net (code "18") (name "CANRX") (class "Default")
      (node (ref "IC7") (pin "4") (pinfunction "RXD_4") (pintype "output"))
      (node (ref "U$1") (pin "PB8") (pinfunction "PB8_PB8") (pintype "bidirectional"))
      (node (ref "U$6") (pin "4") (pinfunction "RXD_4") (pintype "bidirectional"))
    )
    (net (code "19") (name "CANTX") (class "Default")
      (node (ref "IC7") (pin "1") (pinfunction "TXD_1") (pintype "input"))
      (node (ref "U$1") (pin "PB9") (pinfunction "PB9_PB9") (pintype "bidirectional"))
      (node (ref "U$6") (pin "1") (pinfunction "TXD_1") (pintype "bidirectional"))
    )
    (net (code "20") (name "E_CS") (class "Default")
      (node (ref "JP9") (pin "4") (pinfunction "4_4") (pintype "passive"))
      (node (ref "R23") (pin "2") (pinfunction "2_2") (pintype "passive"))
      (node (ref "U$1") (pin "PC10") (pinfunction "PC10_PC10") (pintype "bidirectional"))
    )
    (net (code "21") (name "E_LAT") (class "Default")
      (node (ref "JP10") (pin "1") (pinfunction "1_1") (pintype "passive"))
      (node (ref "R22") (pin "2") (pinfunction "2_2") (pintype "passive"))
      (node (ref "U$1") (pin "PC11") (pinfunction "PC11_PC11") (pintype "bidirectional"))
    )
    (net (code "22") (name "GND") (class "Default")
      (node (ref "AP1509") (pin "4") (pinfunction "SD_4") (pintype "bidirectional"))
      (node (ref "AP1509") (pin "5") (pinfunction "GND1_5") (pintype "power_in"))
      (node (ref "AP1509") (pin "6") (pinfunction "GND2_6") (pintype "power_in"))
      (node (ref "AP1509") (pin "7") (pinfunction "GND3_7") (pintype "power_in"))
      (node (ref "AP1509") (pin "8") (pinfunction "GND4_8") (pintype "power_in"))
      (node (ref "C1") (pin "2") (pinfunction "2_2") (pintype "passive"))
      (node (ref "C10") (pin "2") (pinfunction "2_2") (pintype "passive"))
      (node (ref "C11") (pin "2") (pinfunction "2_2") (pintype "passive"))
      (node (ref "C2") (pin "-") (pinfunction "-_-") (pintype "passive"))
      (node (ref "C3") (pin "2") (pinfunction "2_2") (pintype "passive"))
      (node (ref "C4") (pin "2") (pinfunction "2_2") (pintype "passive"))
      (node (ref "C5") (pin "2") (pinfunction "2_2") (pintype "passive"))
      (node (ref "C6") (pin "2") (pinfunction "2_2") (pintype "passive"))
      (node (ref "C7") (pin "2") (pinfunction "2_2") (pintype "passive"))
      (node (ref "C8") (pin "2") (pinfunction "2_2") (pintype "passive"))
      (node (ref "C9") (pin "2") (pinfunction "2_2") (pintype "passive"))
      (node (ref "D1") (pin "A") (pinfunction "A_A") (pintype "passive"))
      (node (ref "IC1") (pin "6") (pinfunction "INH_6") (pintype "input"))
      (node (ref "IC1") (pin "8") (pinfunction "GND_8") (pintype "power_in"))
      (node (ref "IC10") (pin "2") (pinfunction "GNDSIG_2") (pintype "input"))
      (node (ref "IC10") (pin "3") (pinfunction "~{ON/OFF}_3") (pintype "input"))
      (node (ref "IC10") (pin "4") (pinfunction "GND_4") (pintype "power_in"))
      (node (ref "IC3") (pin "13") (pinfunction "G_13") (pintype "input"))
      (node (ref "IC3") (pin "8") (pinfunction "GND_8") (pintype "power_in"))
      (node (ref "IC4") (pin "6") (pinfunction "INH_6") (pintype "input"))
      (node (ref "IC4") (pin "8") (pinfunction "GND_8") (pintype "power_in"))
      (node (ref "IC5") (pin "13") (pinfunction "G_13") (pintype "input"))
      (node (ref "IC5") (pin "8") (pinfunction "GND_8") (pintype "power_in"))
      (node (ref "IC6") (pin "11") (pinfunction "V-_11") (pintype "power_in"))
      (node (ref "IC7") (pin "2") (pinfunction "GND_2") (pintype "power_in"))
      (node (ref "IC9") (pin "11") (pinfunction "V-_11") (pintype "power_in"))
      (node (ref "J1") (pin "3") (pinfunction "3_3") (pintype "passive"))
      (node (ref "J1") (pin "6") (pinfunction "6_6") (pintype "passive"))
      (node (ref "J1") (pin "7") (pinfunction "7_7") (pintype "passive"))
      (node (ref "J2") (pin "3") (pinfunction "3_3") (pintype "passive"))
      (node (ref "J2") (pin "6") (pinfunction "6_6") (pintype "passive"))
      (node (ref "J2") (pin "7") (pinfunction "7_7") (pintype "passive"))
      (node (ref "J3") (pin "1") (pinfunction "1_1") (pintype "passive"))
      (node (ref "JP10") (pin "4") (pinfunction "4_4") (pintype "passive"))
      (node (ref "JP11") (pin "5") (pinfunction "5_5") (pintype "passive"))
      (node (ref "JP11") (pin "6") (pinfunction "6_6") (pintype "passive"))
      (node (ref "JP12") (pin "5") (pinfunction "5_5") (pintype "passive"))
      (node (ref "JP12") (pin "6") (pinfunction "6_6") (pintype "passive"))
      (node (ref "JP13") (pin "5") (pinfunction "5_5") (pintype "passive"))
      (node (ref "JP14") (pin "5") (pinfunction "5_5") (pintype "passive"))
      (node (ref "JP15") (pin "5") (pinfunction "5_5") (pintype "passive"))
      (node (ref "JP16") (pin "5") (pinfunction "5_5") (pintype "passive"))
      (node (ref "JP16") (pin "6") (pinfunction "6_6") (pintype "passive"))
      (node (ref "JP7") (pin "5") (pinfunction "5_5") (pintype "passive"))
      (node (ref "JP7") (pin "6") (pinfunction "6_6") (pintype "passive"))
      (node (ref "JP8") (pin "4") (pinfunction "4_4") (pintype "passive"))
      (node (ref "Q1") (pin "2") (pinfunction "S_2") (pintype "passive"))
      (node (ref "Q10") (pin "2") (pinfunction "S_2") (pintype "passive"))
      (node (ref "Q11") (pin "2") (pinfunction "S_2") (pintype "passive"))
      (node (ref "Q12") (pin "2") (pinfunction "S_2") (pintype "passive"))
      (node (ref "Q13") (pin "2") (pinfunction "S_2") (pintype "passive"))
      (node (ref "Q14") (pin "2") (pinfunction "S_2") (pintype "passive"))
      (node (ref "Q15") (pin "2") (pinfunction "S_2") (pintype "passive"))
      (node (ref "Q16") (pin "2") (pinfunction "S_2") (pintype "passive"))
      (node (ref "Q2") (pin "2") (pinfunction "S_2") (pintype "passive"))
      (node (ref "Q3") (pin "2") (pinfunction "S_2") (pintype "passive"))
      (node (ref "Q4") (pin "2") (pinfunction "S_2") (pintype "passive"))
      (node (ref "Q5") (pin "2") (pinfunction "S_2") (pintype "passive"))
      (node (ref "Q6") (pin "2") (pinfunction "S_2") (pintype "passive"))
      (node (ref "Q7") (pin "2") (pinfunction "S_2") (pintype "passive"))
      (node (ref "Q8") (pin "2") (pinfunction "S_2") (pintype "passive"))
      (node (ref "Q9") (pin "2") (pinfunction "S_2") (pintype "passive"))
      (node (ref "R2") (pin "1") (pinfunction "1_1") (pintype "passive"))
      (node (ref "R61") (pin "2") (pinfunction "2_2") (pintype "passive"))
      (node (ref "SJ12") (pin "P$2") (pinfunction "2_P$2") (pintype "passive"))
      (node (ref "SJ3") (pin "2") (pinfunction "2_2") (pintype "passive"))
      (node (ref "SJ6") (pin "P$2") (pinfunction "2_P$2") (pintype "passive"))
      (node (ref "SJ9") (pin "2") (pinfunction "2_2") (pintype "passive"))
      (node (ref "U$1") (pin "GND3") (pinfunction "GND3_GND3") (pintype "power_in"))
      (node (ref "U$1") (pin "GND5") (pinfunction "GND5_GND5") (pintype "power_in"))
      (node (ref "U$1") (pin "GND6") (pinfunction "GND6_GND6") (pintype "power_in"))
      (node (ref "U$1") (pin "GND7") (pinfunction "GND7_GND7") (pintype "power_in"))
      (node (ref "U$1") (pin "GND8") (pinfunction "GND8_GND8") (pintype "power_in"))
      (node (ref "U$2") (pin "3") (pinfunction "VSS_3") (pintype "power_in"))
      (node (ref "U$3") (pin "3") (pinfunction "VSS_3") (pintype "power_in"))
      (node (ref "U$4") (pin "3") (pinfunction "VSS_3") (pintype "power_in"))
      (node (ref "U$5") (pin "3") (pinfunction "VSS_3") (pintype "power_in"))
      (node (ref "U$6") (pin "2") (pinfunction "VSS_2") (pintype "power_in"))
      (node (ref "X1") (pin "2") (pinfunction "2_2") (pintype "passive"))
    )
    (net (code "23") (name "I2CSCL") (class "Default")
      (node (ref "JP8") (pin "2") (pinfunction "2_2") (pintype "passive"))
      (node (ref "R63") (pin "2") (pinfunction "2_2") (pintype "passive"))
      (node (ref "U$1") (pin "PB6") (pinfunction "PB6_PB6") (pintype "bidirectional"))
    )
    (net (code "24") (name "I2CSDA") (class "Default")
      (node (ref "JP8") (pin "1") (pinfunction "1_1") (pintype "passive"))
      (node (ref "R62") (pin "2") (pinfunction "2_2") (pintype "passive"))
      (node (ref "U$1") (pin "PB7") (pinfunction "PB7_PB7") (pintype "bidirectional"))
    )
    (net (code "25") (name "ILAT") (class "Default")
      (node (ref "IC1") (pin "15") (pinfunction "SH/~{LD}_15") (pintype "input"))
      (node (ref "IC4") (pin "15") (pinfunction "SH/~{LD}_15") (pintype "input"))
      (node (ref "U$1") (pin "PA6") (pinfunction "PA6_PA6") (pintype "bidirectional"))
    )
    (net (code "26") (name "MISO") (class "Default")
      (node (ref "JP9") (pin "1") (pinfunction "1_1") (pintype "passive"))
      (node (ref "U$1") (pin "PB4") (pinfunction "PB4_PB4") (pintype "bidirectional"))
    )
    (net (code "27") (name "MISO2") (class "Default")
      (node (ref "IC4") (pin "13") (pinfunction "QH_13") (pintype "output"))
      (node (ref "SJ13") (pin "P$2") (pinfunction "2_P$2") (pintype "passive"))
      (node (ref "U$1") (pin "PC2") (pinfunction "PC2_PC2") (pintype "bidirectional"))
    )
    (net (code "28") (name "MOSI") (class "Default")
      (node (ref "IC5") (pin "14") (pinfunction "SER_14") (pintype "input"))
      (node (ref "R20") (pin "1") (pinfunction "1_1") (pintype "passive"))
      (node (ref "SJ15") (pin "1") (pinfunction "1_1") (pintype "passive"))
      (node (ref "SJ17") (pin "P$2") (pinfunction "2_P$2") (pintype "passive"))
      (node (ref "U$1") (pin "PB5") (pinfunction "PB5_PB5") (pintype "bidirectional"))
    )
    (net (code "29") (name "Net-(AP1509-VOUT)") (class "Default")
      (node (ref "AP1509") (pin "2") (pinfunction "VOUT_2") (pintype "bidirectional"))
      (node (ref "D1") (pin "C") (pinfunction "C_C") (pintype "passive"))
      (node (ref "IC10") (pin "7") (pinfunction "OUT_7") (pintype "passive"))
      (node (ref "L1") (pin "2") (pinfunction "2_2") (pintype "passive"))
    )
    (net (code "30") (name "Net-(D2-PadA)") (class "Default")
      (node (ref "D2") (pin "A") (pinfunction "A_A") (pintype "passive"))
      (node (ref "JP4") (pin "4") (pinfunction "4_4") (pintype "passive"))
    )
    (net (code "31") (name "Net-(D2-PadC)") (class "Default")
      (node (ref "D2") (pin "C") (pinfunction "C_C") (pintype "passive"))
      (node (ref "JP4") (pin "1") (pinfunction "1_1") (pintype "passive"))
    )
    (net (code "32") (name "Net-(IC1A-A)") (class "Default")
      (node (ref "IC1") (pin "2") (pinfunction "A_2") (pintype "input"))
      (node (ref "R36") (pin "1") (pinfunction "1_1") (pintype "passive"))
      (node (ref "RN4") (pin "9") (pinfunction "2_9") (pintype "passive"))
    )
    (net (code "33") (name "Net-(IC1A-B)") (class "Default")
      (node (ref "IC1") (pin "3") (pinfunction "B_3") (pintype "input"))
      (node (ref "R37") (pin "1") (pinfunction "1_1") (pintype "passive"))
      (node (ref "RN4") (pin "10") (pinfunction "2_10") (pintype "passive"))
    )
    (net (code "34") (name "Net-(IC1A-C)") (class "Default")
      (node (ref "IC1") (pin "4") (pinfunction "C_4") (pintype "input"))
      (node (ref "R38") (pin "1") (pinfunction "1_1") (pintype "passive"))
      (node (ref "RN4") (pin "11") (pinfunction "2_11") (pintype "passive"))
    )
    (net (code "35") (name "Net-(IC1A-D)") (class "Default")
      (node (ref "IC1") (pin "5") (pinfunction "D_5") (pintype "input"))
      (node (ref "R39") (pin "1") (pinfunction "1_1") (pintype "passive"))
      (node (ref "RN4") (pin "12") (pinfunction "2_12") (pintype "passive"))
    )
    (net (code "36") (name "Net-(IC1A-E)") (class "Default")
      (node (ref "IC1") (pin "10") (pinfunction "E_10") (pintype "input"))
      (node (ref "R41") (pin "1") (pinfunction "1_1") (pintype "passive"))
      (node (ref "RN4") (pin "13") (pinfunction "2_13") (pintype "passive"))
    )
    (net (code "37") (name "Net-(IC1A-F)") (class "Default")
      (node (ref "IC1") (pin "11") (pinfunction "F_11") (pintype "input"))
      (node (ref "R42") (pin "1") (pinfunction "1_1") (pintype "passive"))
      (node (ref "RN4") (pin "14") (pinfunction "2_14") (pintype "passive"))
    )
    (net (code "38") (name "Net-(IC1A-G)") (class "Default")
      (node (ref "IC1") (pin "12") (pinfunction "G_12") (pintype "input"))
      (node (ref "R43") (pin "1") (pinfunction "1_1") (pintype "passive"))
      (node (ref "RN4") (pin "15") (pinfunction "2_15") (pintype "passive"))
    )
    (net (code "39") (name "Net-(IC1A-H)") (class "Default")
      (node (ref "IC1") (pin "14") (pinfunction "H_14") (pintype "input"))
      (node (ref "R44") (pin "1") (pinfunction "1_1") (pintype "passive"))
      (node (ref "RN4") (pin "16") (pinfunction "2_16") (pintype "passive"))
    )
    (net (code "40") (name "Net-(IC2-CD+)") (class "Default")
      (node (ref "IC2") (pin "10") (pinfunction "CD+_10") (pintype "passive"))
      (node (ref "SJ4") (pin "P$1") (pinfunction "1_P$1") (pintype "passive"))
      (node (ref "SJ5") (pin "P$1") (pinfunction "1_P$1") (pintype "passive"))
      (node (ref "SJ6") (pin "P$1") (pinfunction "1_P$1") (pintype "passive"))
    )
    (net (code "41") (name "Net-(IC2-GND)") (class "Default")
      (node (ref "IC2") (pin "9") (pinfunction "GND_9") (pintype "power_in"))
      (node (ref "SJ1") (pin "P$1") (pinfunction "1_P$1") (pintype "passive"))
      (node (ref "SJ2") (pin "P$1") (pinfunction "1_P$1") (pintype "passive"))
      (node (ref "SJ3") (pin "1") (pinfunction "1_1") (pintype "passive"))
    )
    (net (code "42") (name "Net-(IC2-I1)") (class "Default")
      (node (ref "IC2") (pin "1") (pinfunction "I1_1") (pintype "input"))
      (node (ref "IC5") (pin "15") (pinfunction "QA_15") (pintype "tri_state"))
      (node (ref "R3") (pin "1") (pinfunction "1_1") (pintype "passive"))
    )
    (net (code "43") (name "Net-(IC2-I2)") (class "Default")
      (node (ref "IC2") (pin "2") (pinfunction "I2_2") (pintype "input"))
      (node (ref "IC5") (pin "1") (pinfunction "QB_1") (pintype "tri_state"))
      (node (ref "R4") (pin "1") (pinfunction "1_1") (pintype "passive"))
    )
    (net (code "44") (name "Net-(IC2-I3)") (class "Default")
      (node (ref "IC2") (pin "3") (pinfunction "I3_3") (pintype "input"))
      (node (ref "IC5") (pin "2") (pinfunction "QC_2") (pintype "tri_state"))
      (node (ref "R5") (pin "1") (pinfunction "1_1") (pintype "passive"))
    )
    (net (code "45") (name "Net-(IC2-I4)") (class "Default")
      (node (ref "IC2") (pin "4") (pinfunction "I4_4") (pintype "input"))
      (node (ref "IC5") (pin "3") (pinfunction "QD_3") (pintype "tri_state"))
      (node (ref "R6") (pin "1") (pinfunction "1_1") (pintype "passive"))
    )
    (net (code "46") (name "Net-(IC2-I5)") (class "Default")
      (node (ref "IC2") (pin "5") (pinfunction "I5_5") (pintype "input"))
      (node (ref "IC5") (pin "4") (pinfunction "QE_4") (pintype "tri_state"))
      (node (ref "R7") (pin "1") (pinfunction "1_1") (pintype "passive"))
    )
    (net (code "47") (name "Net-(IC2-I6)") (class "Default")
      (node (ref "IC2") (pin "6") (pinfunction "I6_6") (pintype "input"))
      (node (ref "IC5") (pin "5") (pinfunction "QF_5") (pintype "tri_state"))
      (node (ref "R8") (pin "1") (pinfunction "1_1") (pintype "passive"))
    )
    (net (code "48") (name "Net-(IC2-I7)") (class "Default")
      (node (ref "IC2") (pin "7") (pinfunction "I7_7") (pintype "input"))
      (node (ref "IC5") (pin "6") (pinfunction "QG_6") (pintype "tri_state"))
      (node (ref "R9") (pin "1") (pinfunction "1_1") (pintype "passive"))
    )
    (net (code "49") (name "Net-(IC2-I8)") (class "Default")
      (node (ref "IC2") (pin "8") (pinfunction "I8_8") (pintype "input"))
      (node (ref "IC5") (pin "7") (pinfunction "QH_7") (pintype "tri_state"))
      (node (ref "R10") (pin "1") (pinfunction "1_1") (pintype "passive"))
    )
    (net (code "50") (name "Net-(IC2-O1)") (class "Default")
      (node (ref "IC2") (pin "18") (pinfunction "O1_18") (pintype "open_collector"))
      (node (ref "JP1") (pin "1") (pinfunction "1_1") (pintype "passive"))
      (node (ref "Q1") (pin "3") (pinfunction "D_3") (pintype "passive"))
    )
    (net (code "51") (name "Net-(IC2-O2)") (class "Default")
      (node (ref "IC2") (pin "17") (pinfunction "O2_17") (pintype "open_collector"))
      (node (ref "JP1") (pin "2") (pinfunction "2_2") (pintype "passive"))
      (node (ref "Q2") (pin "3") (pinfunction "D_3") (pintype "passive"))
    )
    (net (code "52") (name "Net-(IC2-O3)") (class "Default")
      (node (ref "IC2") (pin "16") (pinfunction "O3_16") (pintype "open_collector"))
      (node (ref "JP1") (pin "3") (pinfunction "3_3") (pintype "passive"))
      (node (ref "Q3") (pin "3") (pinfunction "D_3") (pintype "passive"))
    )
    (net (code "53") (name "Net-(IC2-O4)") (class "Default")
      (node (ref "IC2") (pin "15") (pinfunction "O4_15") (pintype "open_collector"))
      (node (ref "JP1") (pin "4") (pinfunction "4_4") (pintype "passive"))
      (node (ref "Q4") (pin "3") (pinfunction "D_3") (pintype "passive"))
    )
    (net (code "54") (name "Net-(IC2-O5)") (class "Default")
      (node (ref "IC2") (pin "14") (pinfunction "O5_14") (pintype "open_collector"))
      (node (ref "JP1") (pin "5") (pinfunction "5_5") (pintype "passive"))
      (node (ref "Q5") (pin "3") (pinfunction "D_3") (pintype "passive"))
    )
    (net (code "55") (name "Net-(IC2-O6)") (class "Default")
      (node (ref "IC2") (pin "13") (pinfunction "O6_13") (pintype "open_collector"))
      (node (ref "JP1") (pin "6") (pinfunction "6_6") (pintype "passive"))
      (node (ref "Q6") (pin "3") (pinfunction "D_3") (pintype "passive"))
    )
    (net (code "56") (name "Net-(IC2-O7)") (class "Default")
      (node (ref "IC2") (pin "12") (pinfunction "O7_12") (pintype "open_collector"))
      (node (ref "JP1") (pin "7") (pinfunction "7_7") (pintype "passive"))
      (node (ref "Q7") (pin "3") (pinfunction "D_3") (pintype "passive"))
    )
    (net (code "57") (name "Net-(IC2-O8)") (class "Default")
      (node (ref "IC2") (pin "11") (pinfunction "O8_11") (pintype "open_collector"))
      (node (ref "JP1") (pin "8") (pinfunction "8_8") (pintype "passive"))
      (node (ref "Q8") (pin "3") (pinfunction "D_3") (pintype "passive"))
    )
    (net (code "58") (name "Net-(IC3A-QA)") (class "Default")
      (node (ref "IC3") (pin "15") (pinfunction "QA_15") (pintype "tri_state"))
      (node (ref "IC8") (pin "1") (pinfunction "I1_1") (pintype "input"))
      (node (ref "R11") (pin "1") (pinfunction "1_1") (pintype "passive"))
    )
    (net (code "59") (name "Net-(IC3A-QB)") (class "Default")
      (node (ref "IC3") (pin "1") (pinfunction "QB_1") (pintype "tri_state"))
      (node (ref "IC8") (pin "2") (pinfunction "I2_2") (pintype "input"))
      (node (ref "R12") (pin "1") (pinfunction "1_1") (pintype "passive"))
    )
    (net (code "60") (name "Net-(IC3A-QC)") (class "Default")
      (node (ref "IC3") (pin "2") (pinfunction "QC_2") (pintype "tri_state"))
      (node (ref "IC8") (pin "3") (pinfunction "I3_3") (pintype "input"))
      (node (ref "R13") (pin "1") (pinfunction "1_1") (pintype "passive"))
    )
    (net (code "61") (name "Net-(IC3A-QD)") (class "Default")
      (node (ref "IC3") (pin "3") (pinfunction "QD_3") (pintype "tri_state"))
      (node (ref "IC8") (pin "4") (pinfunction "I4_4") (pintype "input"))
      (node (ref "R14") (pin "1") (pinfunction "1_1") (pintype "passive"))
    )
    (net (code "62") (name "Net-(IC3A-QE)") (class "Default")
      (node (ref "IC3") (pin "4") (pinfunction "QE_4") (pintype "tri_state"))
      (node (ref "IC8") (pin "5") (pinfunction "I5_5") (pintype "input"))
      (node (ref "R15") (pin "1") (pinfunction "1_1") (pintype "passive"))
    )
    (net (code "63") (name "Net-(IC3A-QF)") (class "Default")
      (node (ref "IC3") (pin "5") (pinfunction "QF_5") (pintype "tri_state"))
      (node (ref "IC8") (pin "6") (pinfunction "I6_6") (pintype "input"))
      (node (ref "R16") (pin "1") (pinfunction "1_1") (pintype "passive"))
    )
    (net (code "64") (name "Net-(IC3A-QG)") (class "Default")
      (node (ref "IC3") (pin "6") (pinfunction "QG_6") (pintype "tri_state"))
      (node (ref "IC8") (pin "7") (pinfunction "I7_7") (pintype "input"))
      (node (ref "R17") (pin "1") (pinfunction "1_1") (pintype "passive"))
    )
    (net (code "65") (name "Net-(IC3A-QH)") (class "Default")
      (node (ref "IC3") (pin "7") (pinfunction "QH_7") (pintype "tri_state"))
      (node (ref "IC8") (pin "8") (pinfunction "I8_8") (pintype "input"))
      (node (ref "R18") (pin "1") (pinfunction "1_1") (pintype "passive"))
    )
    (net (code "66") (name "Net-(IC4A-A)") (class "Default")
      (node (ref "IC4") (pin "2") (pinfunction "A_2") (pintype "input"))
      (node (ref "R28") (pin "1") (pinfunction "1_1") (pintype "passive"))
      (node (ref "RN1") (pin "9") (pinfunction "2_9") (pintype "passive"))
    )
    (net (code "67") (name "Net-(IC4A-B)") (class "Default")
      (node (ref "IC4") (pin "3") (pinfunction "B_3") (pintype "input"))
      (node (ref "R29") (pin "1") (pinfunction "1_1") (pintype "passive"))
      (node (ref "RN1") (pin "10") (pinfunction "2_10") (pintype "passive"))
    )
    (net (code "68") (name "Net-(IC4A-C)") (class "Default")
      (node (ref "IC4") (pin "4") (pinfunction "C_4") (pintype "input"))
      (node (ref "R30") (pin "1") (pinfunction "1_1") (pintype "passive"))
      (node (ref "RN1") (pin "11") (pinfunction "2_11") (pintype "passive"))
    )
    (net (code "69") (name "Net-(IC4A-D)") (class "Default")
      (node (ref "IC4") (pin "5") (pinfunction "D_5") (pintype "input"))
      (node (ref "R31") (pin "1") (pinfunction "1_1") (pintype "passive"))
      (node (ref "RN1") (pin "12") (pinfunction "2_12") (pintype "passive"))
    )
    (net (code "70") (name "Net-(IC4A-E)") (class "Default")
      (node (ref "IC4") (pin "10") (pinfunction "E_10") (pintype "input"))
      (node (ref "R32") (pin "1") (pinfunction "1_1") (pintype "passive"))
      (node (ref "RN1") (pin "13") (pinfunction "2_13") (pintype "passive"))
    )
    (net (code "71") (name "Net-(IC4A-F)") (class "Default")
      (node (ref "IC4") (pin "11") (pinfunction "F_11") (pintype "input"))
      (node (ref "R33") (pin "1") (pinfunction "1_1") (pintype "passive"))
      (node (ref "RN1") (pin "14") (pinfunction "2_14") (pintype "passive"))
    )
    (net (code "72") (name "Net-(IC4A-G)") (class "Default")
      (node (ref "IC4") (pin "12") (pinfunction "G_12") (pintype "input"))
      (node (ref "R34") (pin "1") (pinfunction "1_1") (pintype "passive"))
      (node (ref "RN1") (pin "15") (pinfunction "2_15") (pintype "passive"))
    )
    (net (code "73") (name "Net-(IC4A-H)") (class "Default")
      (node (ref "IC4") (pin "14") (pinfunction "H_14") (pintype "input"))
      (node (ref "R35") (pin "1") (pinfunction "1_1") (pintype "passive"))
      (node (ref "RN1") (pin "16") (pinfunction "2_16") (pintype "passive"))
    )
    (net (code "74") (name "Net-(IC6A--IN)") (class "Default")
      (node (ref "IC6") (pin "13") (pinfunction "-IN_13") (pintype "input"))
      (node (ref "IC6") (pin "2") (pinfunction "-IN_2") (pintype "input"))
      (node (ref "IC6") (pin "6") (pinfunction "-IN_6") (pintype "input"))
      (node (ref "IC6") (pin "9") (pinfunction "-IN_9") (pintype "input"))
      (node (ref "IC9") (pin "13") (pinfunction "-IN_13") (pintype "input"))
      (node (ref "IC9") (pin "2") (pinfunction "-IN_2") (pintype "input"))
      (node (ref "IC9") (pin "6") (pinfunction "-IN_6") (pintype "input"))
      (node (ref "IC9") (pin "9") (pinfunction "-IN_9") (pintype "input"))
      (node (ref "R1") (pin "1") (pinfunction "1_1") (pintype "passive"))
      (node (ref "R2") (pin "2") (pinfunction "2_2") (pintype "passive"))
    )
    (net (code "75") (name "Net-(IC6A-OUT)") (class "Default")
      (node (ref "IC6") (pin "1") (pinfunction "OUT_1") (pintype "output"))
      (node (ref "JP15") (pin "3") (pinfunction "3_3") (pintype "passive"))
      (node (ref "JP5") (pin "3") (pinfunction "3_3") (pintype "passive"))
      (node (ref "U$5") (pin "5") (pinfunction "O_5") (pintype "output"))
    )
    (net (code "76") (name "Net-(IC6B-OUT)") (class "Default")
      (node (ref "IC6") (pin "7") (pinfunction "OUT_7") (pintype "output"))
      (node (ref "JP15") (pin "1") (pinfunction "1_1") (pintype "passive"))
      (node (ref "JP5") (pin "1") (pinfunction "1_1") (pintype "passive"))
      (node (ref "U$4") (pin "7") (pinfunction "O_7") (pintype "output"))
    )
    (net (code "77") (name "Net-(IC6C-OUT)") (class "Default")
      (node (ref "IC6") (pin "8") (pinfunction "OUT_8") (pintype "output"))
      (node (ref "JP15") (pin "2") (pinfunction "2_2") (pintype "passive"))
      (node (ref "JP5") (pin "2") (pinfunction "2_2") (pintype "passive"))
      (node (ref "U$4") (pin "5") (pinfunction "O_5") (pintype "output"))
    )
    (net (code "78") (name "Net-(IC6D-OUT)") (class "Default")
      (node (ref "IC6") (pin "14") (pinfunction "OUT_14") (pintype "output"))
      (node (ref "JP15") (pin "4") (pinfunction "4_4") (pintype "passive"))
      (node (ref "JP5") (pin "4") (pinfunction "4_4") (pintype "passive"))
      (node (ref "U$5") (pin "7") (pinfunction "O_7") (pintype "output"))
    )
    (net (code "79") (name "Net-(IC7-RS)") (class "Default")
      (node (ref "IC7") (pin "8") (pinfunction "RS_8") (pintype "input"))
      (node (ref "R61") (pin "1") (pinfunction "1_1") (pintype "passive"))
      (node (ref "U$6") (pin "8") (pinfunction "RS_8") (pintype "bidirectional"))
    )
    (net (code "80") (name "Net-(IC7-VREF)") (class "Default")
      (node (ref "IC7") (pin "5") (pinfunction "VREF_5") (pintype "output"))
      (node (ref "SJ18") (pin "P$2") (pinfunction "2_P$2") (pintype "passive"))
      (node (ref "U$6") (pin "5") (pinfunction "VREF_5") (pintype "bidirectional"))
    )
    (net (code "81") (name "Net-(IC8-CD+)") (class "Default")
      (node (ref "IC8") (pin "10") (pinfunction "CD+_10") (pintype "passive"))
      (node (ref "SJ10") (pin "P$1") (pinfunction "1_P$1") (pintype "passive"))
      (node (ref "SJ11") (pin "P$1") (pinfunction "1_P$1") (pintype "passive"))
      (node (ref "SJ12") (pin "P$1") (pinfunction "1_P$1") (pintype "passive"))
    )
    (net (code "82") (name "Net-(IC8-GND)") (class "Default")
      (node (ref "IC8") (pin "9") (pinfunction "GND_9") (pintype "power_in"))
      (node (ref "SJ7") (pin "P$1") (pinfunction "1_P$1") (pintype "passive"))
      (node (ref "SJ8") (pin "P$1") (pinfunction "1_P$1") (pintype "passive"))
      (node (ref "SJ9") (pin "1") (pinfunction "1_1") (pintype "passive"))
    )
    (net (code "83") (name "Net-(IC8-O1)") (class "Default")
      (node (ref "IC8") (pin "18") (pinfunction "O1_18") (pintype "open_collector"))
      (node (ref "JP6") (pin "1") (pinfunction "1_1") (pintype "passive"))
      (node (ref "Q9") (pin "3") (pinfunction "D_3") (pintype "passive"))
    )
    (net (code "84") (name "Net-(IC8-O2)") (class "Default")
      (node (ref "IC8") (pin "17") (pinfunction "O2_17") (pintype "open_collector"))
      (node (ref "JP6") (pin "2") (pinfunction "2_2") (pintype "passive"))
      (node (ref "Q10") (pin "3") (pinfunction "D_3") (pintype "passive"))
    )
    (net (code "85") (name "Net-(IC8-O3)") (class "Default")
      (node (ref "IC8") (pin "16") (pinfunction "O3_16") (pintype "open_collector"))
      (node (ref "JP6") (pin "3") (pinfunction "3_3") (pintype "passive"))
      (node (ref "Q11") (pin "3") (pinfunction "D_3") (pintype "passive"))
    )
    (net (code "86") (name "Net-(IC8-O4)") (class "Default")
      (node (ref "IC8") (pin "15") (pinfunction "O4_15") (pintype "open_collector"))
      (node (ref "JP6") (pin "4") (pinfunction "4_4") (pintype "passive"))
      (node (ref "Q12") (pin "3") (pinfunction "D_3") (pintype "passive"))
    )
    (net (code "87") (name "Net-(IC8-O5)") (class "Default")
      (node (ref "IC8") (pin "14") (pinfunction "O5_14") (pintype "open_collector"))
      (node (ref "JP6") (pin "5") (pinfunction "5_5") (pintype "passive"))
      (node (ref "Q13") (pin "3") (pinfunction "D_3") (pintype "passive"))
    )
    (net (code "88") (name "Net-(IC8-O6)") (class "Default")
      (node (ref "IC8") (pin "13") (pinfunction "O6_13") (pintype "open_collector"))
      (node (ref "JP6") (pin "6") (pinfunction "6_6") (pintype "passive"))
      (node (ref "Q14") (pin "3") (pinfunction "D_3") (pintype "passive"))
    )
    (net (code "89") (name "Net-(IC8-O7)") (class "Default")
      (node (ref "IC8") (pin "12") (pinfunction "O7_12") (pintype "open_collector"))
      (node (ref "JP6") (pin "7") (pinfunction "7_7") (pintype "passive"))
      (node (ref "Q15") (pin "3") (pinfunction "D_3") (pintype "passive"))
    )
    (net (code "90") (name "Net-(IC8-O8)") (class "Default")
      (node (ref "IC8") (pin "11") (pinfunction "O8_11") (pintype "open_collector"))
      (node (ref "JP6") (pin "8") (pinfunction "8_8") (pintype "passive"))
      (node (ref "Q16") (pin "3") (pinfunction "D_3") (pintype "passive"))
    )
    (net (code "91") (name "Net-(IC9A-OUT)") (class "Default")
      (node (ref "IC9") (pin "1") (pinfunction "OUT_1") (pintype "output"))
      (node (ref "JP15") (pin "9") (pinfunction "9_9") (pintype "passive"))
      (node (ref "JP5") (pin "7") (pinfunction "7_7") (pintype "passive"))
      (node (ref "U$3") (pin "5") (pinfunction "O_5") (pintype "output"))
    )
    (net (code "92") (name "Net-(IC9B-OUT)") (class "Default")
      (node (ref "IC9") (pin "7") (pinfunction "OUT_7") (pintype "output"))
      (node (ref "JP15") (pin "7") (pinfunction "7_7") (pintype "passive"))
      (node (ref "JP5") (pin "5") (pinfunction "5_5") (pintype "passive"))
      (node (ref "U$2") (pin "7") (pinfunction "O_7") (pintype "output"))
    )
    (net (code "93") (name "Net-(IC9C-OUT)") (class "Default")
      (node (ref "IC9") (pin "8") (pinfunction "OUT_8") (pintype "output"))
      (node (ref "JP15") (pin "8") (pinfunction "8_8") (pintype "passive"))
      (node (ref "JP5") (pin "6") (pinfunction "6_6") (pintype "passive"))
      (node (ref "U$2") (pin "5") (pinfunction "O_5") (pintype "output"))
    )
    (net (code "94") (name "Net-(IC9D-OUT)") (class "Default")
      (node (ref "IC9") (pin "14") (pinfunction "OUT_14") (pintype "output"))
      (node (ref "JP15") (pin "10") (pinfunction "10_10") (pintype "passive"))
      (node (ref "JP5") (pin "8") (pinfunction "8_8") (pintype "passive"))
      (node (ref "U$3") (pin "7") (pinfunction "O_7") (pintype "output"))
    )
    (net (code "95") (name "Net-(J1-Pad4)") (class "Default")
      (node (ref "J1") (pin "4") (pinfunction "4_4") (pintype "passive"))
      (node (ref "J2") (pin "4") (pinfunction "4_4") (pintype "passive"))
    )
    (net (code "96") (name "Net-(J1-Pad5)") (class "Default")
      (node (ref "J1") (pin "5") (pinfunction "5_5") (pintype "passive"))
      (node (ref "J2") (pin "5") (pinfunction "5_5") (pintype "passive"))
    )
    (net (code "97") (name "Net-(J1-Pad8)") (class "Default")
      (node (ref "J1") (pin "8") (pinfunction "8_8") (pintype "passive"))
      (node (ref "J2") (pin "8") (pinfunction "8_8") (pintype "passive"))
      (node (ref "R40") (pin "1") (pinfunction "1_1") (pintype "passive"))
    )
    (net (code "98") (name "Net-(JP4-Pad3)") (class "Default")
      (node (ref "JP4") (pin "3") (pinfunction "3_3") (pintype "passive"))
      (node (ref "R40") (pin "2") (pinfunction "2_2") (pintype "passive"))
    )
    (net (code "99") (name "Net-(JP13-Pad1)") (class "Default")
      (node (ref "JP13") (pin "1") (pinfunction "1_1") (pintype "passive"))
      (node (ref "JP3") (pin "1") (pinfunction "1_1") (pintype "passive"))
      (node (ref "R44") (pin "2") (pinfunction "2_2") (pintype "passive"))
      (node (ref "R53") (pin "2") (pinfunction "2_2") (pintype "passive"))
      (node (ref "RN4") (pin "1") (pinfunction "1_1") (pintype "passive"))
      (node (ref "RN5") (pin "9") (pinfunction "9_9") (pintype "passive"))
    )
    (net (code "100") (name "Net-(JP14-Pad1)") (class "Default")
      (node (ref "JP14") (pin "1") (pinfunction "1_1") (pintype "passive"))
      (node (ref "JP2") (pin "1") (pinfunction "1_1") (pintype "passive"))
      (node (ref "R35") (pin "2") (pinfunction "2_2") (pintype "passive"))
      (node (ref "R45") (pin "2") (pinfunction "2_2") (pintype "passive"))
      (node (ref "RN1") (pin "1") (pinfunction "1_1") (pintype "passive"))
      (node (ref "RN2") (pin "9") (pinfunction "9_9") (pintype "passive"))
    )
    (net (code "101") (name "Net-(Q1-G)") (class "Default")
      (node (ref "Q1") (pin "1") (pinfunction "G_1") (pintype "passive"))
      (node (ref "R3") (pin "2") (pinfunction "2_2") (pintype "passive"))
    )
    (net (code "102") (name "Net-(Q2-G)") (class "Default")
      (node (ref "Q2") (pin "1") (pinfunction "G_1") (pintype "passive"))
      (node (ref "R4") (pin "2") (pinfunction "2_2") (pintype "passive"))
    )
    (net (code "103") (name "Net-(Q3-G)") (class "Default")
      (node (ref "Q3") (pin "1") (pinfunction "G_1") (pintype "passive"))
      (node (ref "R5") (pin "2") (pinfunction "2_2") (pintype "passive"))
    )
    (net (code "104") (name "Net-(Q4-G)") (class "Default")
      (node (ref "Q4") (pin "1") (pinfunction "G_1") (pintype "passive"))
      (node (ref "R6") (pin "2") (pinfunction "2_2") (pintype "passive"))
    )
    (net (code "105") (name "Net-(Q5-G)") (class "Default")
      (node (ref "Q5") (pin "1") (pinfunction "G_1") (pintype "passive"))
      (node (ref "R7") (pin "2") (pinfunction "2_2") (pintype "passive"))
    )
    (net (code "106") (name "Net-(Q6-G)") (class "Default")
      (node (ref "Q6") (pin "1") (pinfunction "G_1") (pintype "passive"))
      (node (ref "R8") (pin "2") (pinfunction "2_2") (pintype "passive"))
    )
    (net (code "107") (name "Net-(Q7-G)") (class "Default")
      (node (ref "Q7") (pin "1") (pinfunction "G_1") (pintype "passive"))
      (node (ref "R9") (pin "2") (pinfunction "2_2") (pintype "passive"))
    )
    (net (code "108") (name "Net-(Q8-G)") (class "Default")
      (node (ref "Q8") (pin "1") (pinfunction "G_1") (pintype "passive"))
      (node (ref "R10") (pin "2") (pinfunction "2_2") (pintype "passive"))
    )
    (net (code "109") (name "Net-(Q9-G)") (class "Default")
      (node (ref "Q9") (pin "1") (pinfunction "G_1") (pintype "passive"))
      (node (ref "R11") (pin "2") (pinfunction "2_2") (pintype "passive"))
    )
    (net (code "110") (name "Net-(Q10-G)") (class "Default")
      (node (ref "Q10") (pin "1") (pinfunction "G_1") (pintype "passive"))
      (node (ref "R12") (pin "2") (pinfunction "2_2") (pintype "passive"))
    )
    (net (code "111") (name "Net-(Q11-G)") (class "Default")
      (node (ref "Q11") (pin "1") (pinfunction "G_1") (pintype "passive"))
      (node (ref "R13") (pin "2") (pinfunction "2_2") (pintype "passive"))
    )
    (net (code "112") (name "Net-(Q12-G)") (class "Default")
      (node (ref "Q12") (pin "1") (pinfunction "G_1") (pintype "passive"))
      (node (ref "R14") (pin "2") (pinfunction "2_2") (pintype "passive"))
    )
    (net (code "113") (name "Net-(Q13-G)") (class "Default")
      (node (ref "Q13") (pin "1") (pinfunction "G_1") (pintype "passive"))
      (node (ref "R15") (pin "2") (pinfunction "2_2") (pintype "passive"))
    )
    (net (code "114") (name "Net-(Q14-G)") (class "Default")
      (node (ref "Q14") (pin "1") (pinfunction "G_1") (pintype "passive"))
      (node (ref "R16") (pin "2") (pinfunction "2_2") (pintype "passive"))
    )
    (net (code "115") (name "Net-(Q15-G)") (class "Default")
      (node (ref "Q15") (pin "1") (pinfunction "G_1") (pintype "passive"))
      (node (ref "R17") (pin "2") (pinfunction "2_2") (pintype "passive"))
    )
    (net (code "116") (name "Net-(Q16-G)") (class "Default")
      (node (ref "Q16") (pin "1") (pinfunction "G_1") (pintype "passive"))
      (node (ref "R18") (pin "2") (pinfunction "2_2") (pintype "passive"))
    )
    (net (code "117") (name "Net-(RN1B-1)") (class "Default")
      (node (ref "JP14") (pin "2") (pinfunction "2_2") (pintype "passive"))
      (node (ref "JP2") (pin "2") (pinfunction "2_2") (pintype "passive"))
      (node (ref "R34") (pin "2") (pinfunction "2_2") (pintype "passive"))
      (node (ref "R46") (pin "1") (pinfunction "1_1") (pintype "passive"))
      (node (ref "RN1") (pin "2") (pinfunction "1_2") (pintype "passive"))
      (node (ref "RN2") (pin "8") (pinfunction "8_8") (pintype "passive"))
    )
    (net (code "118") (name "Net-(RN1C-1)") (class "Default")
      (node (ref "JP14") (pin "3") (pinfunction "3_3") (pintype "passive"))
      (node (ref "JP2") (pin "3") (pinfunction "3_3") (pintype "passive"))
      (node (ref "R33") (pin "2") (pinfunction "2_2") (pintype "passive"))
      (node (ref "R47") (pin "1") (pinfunction "1_1") (pintype "passive"))
      (node (ref "RN1") (pin "3") (pinfunction "1_3") (pintype "passive"))
      (node (ref "RN2") (pin "7") (pinfunction "7_7") (pintype "passive"))
    )
    (net (code "119") (name "Net-(RN1D-1)") (class "Default")
      (node (ref "JP14") (pin "4") (pinfunction "4_4") (pintype "passive"))
      (node (ref "JP2") (pin "4") (pinfunction "4_4") (pintype "passive"))
      (node (ref "R32") (pin "2") (pinfunction "2_2") (pintype "passive"))
      (node (ref "R48") (pin "1") (pinfunction "1_1") (pintype "passive"))
      (node (ref "RN1") (pin "4") (pinfunction "1_4") (pintype "passive"))
      (node (ref "RN2") (pin "6") (pinfunction "6_6") (pintype "passive"))
    )
    (net (code "120") (name "Net-(RN1E-1)") (class "Default")
      (node (ref "JP14") (pin "7") (pinfunction "7_7") (pintype "passive"))
      (node (ref "JP2") (pin "5") (pinfunction "5_5") (pintype "passive"))
      (node (ref "R31") (pin "2") (pinfunction "2_2") (pintype "passive"))
      (node (ref "R49") (pin "1") (pinfunction "1_1") (pintype "passive"))
      (node (ref "RN1") (pin "5") (pinfunction "1_5") (pintype "passive"))
      (node (ref "RN2") (pin "5") (pinfunction "5_5") (pintype "passive"))
    )
    (net (code "121") (name "Net-(RN1F-1)") (class "Default")
      (node (ref "JP14") (pin "8") (pinfunction "8_8") (pintype "passive"))
      (node (ref "JP2") (pin "6") (pinfunction "6_6") (pintype "passive"))
      (node (ref "R30") (pin "2") (pinfunction "2_2") (pintype "passive"))
      (node (ref "R50") (pin "1") (pinfunction "1_1") (pintype "passive"))
      (node (ref "RN1") (pin "6") (pinfunction "1_6") (pintype "passive"))
      (node (ref "RN2") (pin "4") (pinfunction "4_4") (pintype "passive"))
    )
    (net (code "122") (name "Net-(RN1G-1)") (class "Default")
      (node (ref "JP14") (pin "9") (pinfunction "9_9") (pintype "passive"))
      (node (ref "JP2") (pin "7") (pinfunction "7_7") (pintype "passive"))
      (node (ref "R29") (pin "2") (pinfunction "2_2") (pintype "passive"))
      (node (ref "R51") (pin "1") (pinfunction "1_1") (pintype "passive"))
      (node (ref "RN1") (pin "7") (pinfunction "1_7") (pintype "passive"))
      (node (ref "RN2") (pin "3") (pinfunction "3_3") (pintype "passive"))
    )
    (net (code "123") (name "Net-(RN1H-1)") (class "Default")
      (node (ref "JP14") (pin "10") (pinfunction "10_10") (pintype "passive"))
      (node (ref "JP2") (pin "8") (pinfunction "8_8") (pintype "passive"))
      (node (ref "R28") (pin "2") (pinfunction "2_2") (pintype "passive"))
      (node (ref "R52") (pin "1") (pinfunction "1_1") (pintype "passive"))
      (node (ref "RN1") (pin "8") (pinfunction "1_8") (pintype "passive"))
      (node (ref "RN2") (pin "2") (pinfunction "2_2") (pintype "passive"))
    )
    (net (code "124") (name "Net-(RN4B-1)") (class "Default")
      (node (ref "JP13") (pin "2") (pinfunction "2_2") (pintype "passive"))
      (node (ref "JP3") (pin "2") (pinfunction "2_2") (pintype "passive"))
      (node (ref "R43") (pin "2") (pinfunction "2_2") (pintype "passive"))
      (node (ref "R54") (pin "2") (pinfunction "2_2") (pintype "passive"))
      (node (ref "RN4") (pin "2") (pinfunction "1_2") (pintype "passive"))
      (node (ref "RN5") (pin "8") (pinfunction "8_8") (pintype "passive"))
    )
    (net (code "125") (name "Net-(RN4C-1)") (class "Default")
      (node (ref "JP13") (pin "3") (pinfunction "3_3") (pintype "passive"))
      (node (ref "JP3") (pin "3") (pinfunction "3_3") (pintype "passive"))
      (node (ref "R42") (pin "2") (pinfunction "2_2") (pintype "passive"))
      (node (ref "R55") (pin "2") (pinfunction "2_2") (pintype "passive"))
      (node (ref "RN4") (pin "3") (pinfunction "1_3") (pintype "passive"))
      (node (ref "RN5") (pin "7") (pinfunction "7_7") (pintype "passive"))
    )
    (net (code "126") (name "Net-(RN4D-1)") (class "Default")
      (node (ref "JP13") (pin "4") (pinfunction "4_4") (pintype "passive"))
      (node (ref "JP3") (pin "4") (pinfunction "4_4") (pintype "passive"))
      (node (ref "R41") (pin "2") (pinfunction "2_2") (pintype "passive"))
      (node (ref "R56") (pin "2") (pinfunction "2_2") (pintype "passive"))
      (node (ref "RN4") (pin "4") (pinfunction "1_4") (pintype "passive"))
      (node (ref "RN5") (pin "6") (pinfunction "6_6") (pintype "passive"))
    )
    (net (code "127") (name "Net-(RN4E-1)") (class "Default")
      (node (ref "JP13") (pin "7") (pinfunction "7_7") (pintype "passive"))
      (node (ref "JP3") (pin "5") (pinfunction "5_5") (pintype "passive"))
      (node (ref "R39") (pin "2") (pinfunction "2_2") (pintype "passive"))
      (node (ref "R57") (pin "2") (pinfunction "2_2") (pintype "passive"))
      (node (ref "RN4") (pin "5") (pinfunction "1_5") (pintype "passive"))
      (node (ref "RN5") (pin "5") (pinfunction "5_5") (pintype "passive"))
    )
    (net (code "128") (name "Net-(RN4F-1)") (class "Default")
      (node (ref "JP13") (pin "8") (pinfunction "8_8") (pintype "passive"))
      (node (ref "JP3") (pin "6") (pinfunction "6_6") (pintype "passive"))
      (node (ref "R38") (pin "2") (pinfunction "2_2") (pintype "passive"))
      (node (ref "R58") (pin "2") (pinfunction "2_2") (pintype "passive"))
      (node (ref "RN4") (pin "6") (pinfunction "1_6") (pintype "passive"))
      (node (ref "RN5") (pin "4") (pinfunction "4_4") (pintype "passive"))
    )
    (net (code "129") (name "Net-(RN4G-1)") (class "Default")
      (node (ref "JP13") (pin "9") (pinfunction "9_9") (pintype "passive"))
      (node (ref "JP3") (pin "7") (pinfunction "7_7") (pintype "passive"))
      (node (ref "R37") (pin "2") (pinfunction "2_2") (pintype "passive"))
      (node (ref "R59") (pin "2") (pinfunction "2_2") (pintype "passive"))
      (node (ref "RN4") (pin "7") (pinfunction "1_7") (pintype "passive"))
      (node (ref "RN5") (pin "3") (pinfunction "3_3") (pintype "passive"))
    )
    (net (code "130") (name "Net-(RN4H-1)") (class "Default")
      (node (ref "JP13") (pin "10") (pinfunction "10_10") (pintype "passive"))
      (node (ref "JP3") (pin "8") (pinfunction "8_8") (pintype "passive"))
      (node (ref "R36") (pin "2") (pinfunction "2_2") (pintype "passive"))
      (node (ref "R60") (pin "2") (pinfunction "2_2") (pintype "passive"))
      (node (ref "RN4") (pin "8") (pinfunction "1_8") (pintype "passive"))
      (node (ref "RN5") (pin "2") (pinfunction "2_2") (pintype "passive"))
    )
    (net (code "131") (name "Net-(SJ13-1)") (class "Default")
      (node (ref "SJ13") (pin "P$1") (pinfunction "1_P$1") (pintype "passive"))
      (node (ref "U$1") (pin "PB14") (pinfunction "PB14_PB14") (pintype "bidirectional"))
    )
    (net (code "132") (name "Net-(SJ14-1)") (class "Default")
      (node (ref "SJ14") (pin "P$1") (pinfunction "1_P$1") (pintype "passive"))
      (node (ref "U$1") (pin "VIN2") (pinfunction "VIN2_VIN2") (pintype "power_in"))
    )
    (net (code "133") (name "Net-(SJ16-2)") (class "Default")
      (node (ref "JP9") (pin "2") (pinfunction "2_2") (pintype "passive"))
      (node (ref "SJ15") (pin "2") (pinfunction "2_2") (pintype "passive"))
      (node (ref "SJ16") (pin "P$2") (pinfunction "2_P$2") (pintype "passive"))
    )
    (net (code "134") (name "OLAT") (class "Default")
      (node (ref "IC3") (pin "12") (pinfunction "RCK_12") (pintype "input"))
      (node (ref "IC5") (pin "12") (pinfunction "RCK_12") (pintype "input"))
      (node (ref "R21") (pin "1") (pinfunction "1_1") (pintype "passive"))
      (node (ref "U$1") (pin "PA8") (pinfunction "PA8_PA8") (pintype "bidirectional"))
    )
    (net (code "135") (name "SCK") (class "Default")
      (node (ref "IC3") (pin "11") (pinfunction "SCK_11") (pintype "input"))
      (node (ref "IC5") (pin "11") (pinfunction "SCK_11") (pintype "input"))
      (node (ref "JP9") (pin "3") (pinfunction "3_3") (pintype "passive"))
      (node (ref "R19") (pin "1") (pinfunction "1_1") (pintype "passive"))
      (node (ref "U$1") (pin "PB3") (pinfunction "PB3_PB3") (pintype "bidirectional"))
    )
    (net (code "136") (name "SCK2") (class "Default")
      (node (ref "IC1") (pin "7") (pinfunction "CLK_7") (pintype "input"))
      (node (ref "IC4") (pin "7") (pinfunction "CLK_7") (pintype "input"))
      (node (ref "U$1") (pin "PB10") (pinfunction "PB10_PB10") (pintype "bidirectional"))
    )
    (net (code "137") (name "SLNK1") (class "Default")
      (node (ref "IC3") (pin "14") (pinfunction "SER_14") (pintype "input"))
      (node (ref "IC5") (pin "9") (pinfunction "QH*_9") (pintype "tri_state"))
      (node (ref "SJ17") (pin "P$1") (pinfunction "1_P$1") (pintype "passive"))
    )
    (net (code "138") (name "SLNK2") (class "Default")
      (node (ref "IC3") (pin "9") (pinfunction "QH*_9") (pintype "tri_state"))
      (node (ref "SJ16") (pin "P$1") (pinfunction "1_P$1") (pintype "passive"))
    )
    (net (code "139") (name "SLNK3") (class "Default")
      (node (ref "IC1") (pin "13") (pinfunction "QH_13") (pintype "output"))
      (node (ref "IC4") (pin "1") (pinfunction "SER_1") (pintype "input"))
    )
    (net (code "140") (name "SRV1") (class "Default")
      (node (ref "JP7") (pin "2") (pinfunction "2_2") (pintype "passive"))
      (node (ref "R25") (pin "2") (pinfunction "2_2") (pintype "passive"))
      (node (ref "U$1") (pin "PC9") (pinfunction "PC9_PC9") (pintype "bidirectional"))
    )
    (net (code "141") (name "SRV2") (class "Default")
      (node (ref "JP7") (pin "1") (pinfunction "1_1") (pintype "passive"))
      (node (ref "R24") (pin "2") (pinfunction "2_2") (pintype "passive"))
      (node (ref "U$1") (pin "PC7") (pinfunction "PC7_PC7") (pintype "bidirectional"))
    )
    (net (code "142") (name "SRV3") (class "Default")
      (node (ref "JP11") (pin "2") (pinfunction "2_2") (pintype "passive"))
      (node (ref "R26") (pin "2") (pinfunction "2_2") (pintype "passive"))
      (node (ref "U$1") (pin "PC8") (pinfunction "PC8_PC8") (pintype "bidirectional"))
    )
    (net (code "143") (name "SRV4") (class "Default")
      (node (ref "JP11") (pin "1") (pinfunction "1_1") (pintype "passive"))
      (node (ref "R27") (pin "2") (pinfunction "2_2") (pintype "passive"))
      (node (ref "U$1") (pin "PC6") (pinfunction "PC6_PC6") (pintype "bidirectional"))
    )
    (net (code "144") (name "SRV5") (class "Default")
      (node (ref "JP12") (pin "2") (pinfunction "2_2") (pintype "passive"))
      (node (ref "R64") (pin "2") (pinfunction "2_2") (pintype "passive"))
      (node (ref "U$1") (pin "PF1-PH1") (pinfunction "PF1-PH1_PF1-PH1") (pintype "bidirectional"))
    )
    (net (code "145") (name "SRV6") (class "Default")
      (node (ref "JP12") (pin "1") (pinfunction "1_1") (pintype "passive"))
      (node (ref "R65") (pin "2") (pinfunction "2_2") (pintype "passive"))
      (node (ref "U$1") (pin "PA15") (pinfunction "PA15_PA15") (pintype "bidirectional"))
    )
    (net (code "146") (name "SRV7") (class "Default")
      (node (ref "JP16") (pin "2") (pinfunction "2_2") (pintype "passive"))
      (node (ref "R66") (pin "2") (pinfunction "2_2") (pintype "passive"))
      (node (ref "U$1") (pin "PC12") (pinfunction "PC12_PC12") (pintype "bidirectional"))
    )
    (net (code "147") (name "SRV8") (class "Default")
      (node (ref "JP16") (pin "1") (pinfunction "1_1") (pintype "passive"))
      (node (ref "R67") (pin "2") (pinfunction "2_2") (pintype "passive"))
      (node (ref "U$1") (pin "PD2") (pinfunction "PD2_PD2") (pintype "bidirectional"))
    )
    (net (code "148") (name "TIN3") (class "Default")
      (node (ref "IC9") (pin "10") (pinfunction "+IN_10") (pintype "input"))
      (node (ref "U$1") (pin "PB15") (pinfunction "PB15_PB15") (pintype "bidirectional"))
      (node (ref "U$2") (pin "4") (pinfunction "I_4") (pintype "input"))
    )
    (net (code "149") (name "TIN4") (class "Default")
      (node (ref "IC9") (pin "12") (pinfunction "+IN_12") (pintype "input"))
      (node (ref "U$1") (pin "PB12") (pinfunction "PB12_PB12") (pintype "bidirectional"))
      (node (ref "U$3") (pin "2") (pinfunction "I_2") (pintype "input"))
    )
    (net (code "150") (name "V+") (class "Default")
      (node (ref "AP1509") (pin "3") (pinfunction "FB_3") (pintype "bidirectional"))
      (node (ref "C1") (pin "1") (pinfunction "1_1") (pintype "passive"))
      (node (ref "C2") (pin "+") (pinfunction "+_+") (pintype "passive"))
      (node (ref "IC10") (pin "1") (pinfunction "FB_1") (pintype "input"))
      (node (ref "L1") (pin "1") (pinfunction "1_1") (pintype "passive"))
      (node (ref "U$1") (pin "E5V") (pinfunction "E5V_E5V") (pintype "power_in"))
    )
    (net (code "151") (name "unconnected-(H1-MOUNT-PadB3,3)") (class "Default")
      (node (ref "H1") (pin "B3,3") (pinfunction "MOUNT_B3,3") (pintype "passive"))
    )
    (net (code "152") (name "unconnected-(H2-MOUNT-PadB3,3)") (class "Default")
      (node (ref "H2") (pin "B3,3") (pinfunction "MOUNT_B3,3") (pintype "passive"))
    )
    (net (code "153") (name "unconnected-(H3-MOUNT-PadB3,3)") (class "Default")
      (node (ref "H3") (pin "B3,3") (pinfunction "MOUNT_B3,3") (pintype "passive"))
    )
    (net (code "154") (name "unconnected-(H4-MOUNT-PadB3,3)") (class "Default")
      (node (ref "H4") (pin "B3,3") (pinfunction "MOUNT_B3,3") (pintype "passive"))
    )
    (net (code "155") (name "unconnected-(J3-Pad2)") (class "Default")
      (node (ref "J3") (pin "2") (pinfunction "2_2") (pintype "passive"))
    )
    (net (code "156") (name "unconnected-(U$1-PadBOOT0)") (class "Default")
      (node (ref "U$1") (pin "BOOT0") (pinfunction "BOOT0_BOOT0") (pintype "bidirectional"))
    )
    (net (code "157") (name "unconnected-(U$1-PadIOREF2)") (class "Default")
      (node (ref "U$1") (pin "IOREF2") (pinfunction "IOREF2_IOREF2") (pintype "input"))
    )
    (net (code "158") (name "unconnected-(U$1-PadNC1-PF7)") (class "Default")
      (node (ref "U$1") (pin "NC1-PF7") (pinfunction "NC1-PF7_NC1-PF7") (pintype "bidirectional"))
    )
    (net (code "159") (name "unconnected-(U$1-PadNC2-PF6)") (class "Default")
      (node (ref "U$1") (pin "NC2-PF6") (pinfunction "NC2-PF6_NC2-PF6") (pintype "bidirectional"))
    )
    (net (code "160") (name "unconnected-(U$1-PadNC3)") (class "Default")
      (node (ref "U$1") (pin "NC3") (pinfunction "NC3_NC3") (pintype "no_connect"))
    )
    (net (code "161") (name "unconnected-(U$1-PadNC4)") (class "Default")
      (node (ref "U$1") (pin "NC4") (pinfunction "NC4_NC4") (pintype "no_connect"))
    )
    (net (code "162") (name "unconnected-(U$1-PadNC5-PD8)") (class "Default")
      (node (ref "U$1") (pin "NC5-PD8") (pinfunction "NC5-PD8_NC5-PD8") (pintype "bidirectional"))
    )
    (net (code "163") (name "unconnected-(U$1-PadNC6-PB11)") (class "Default")
      (node (ref "U$1") (pin "NC6-PB11") (pinfunction "NC6-PB11_NC6-PB11") (pintype "no_connect"))
    )
    (net (code "164") (name "unconnected-(U$1-PadNC7-PF5)") (class "Default")
      (node (ref "U$1") (pin "NC7-PF5") (pinfunction "NC7-PF5_NC7-PF5") (pintype "bidirectional"))
    )
    (net (code "165") (name "unconnected-(U$1-PadNC8-PF4)") (class "Default")
      (node (ref "U$1") (pin "NC8-PF4") (pinfunction "NC8-PF4_NC8-PF4") (pintype "bidirectional"))
    )
    (net (code "166") (name "unconnected-(U$1-PadNRESET)") (class "Default")
      (node (ref "U$1") (pin "NRESET") (pinfunction "NRESET_NRESET") (pintype "input"))
    )
    (net (code "167") (name "unconnected-(U$1-PadPA1)") (class "Default")
      (node (ref "U$1") (pin "PA1") (pinfunction "PA1_PA1") (pintype "bidirectional"))
    )
    (net (code "168") (name "unconnected-(U$1-PadPA2)") (class "Default")
      (node (ref "U$1") (pin "PA2") (pinfunction "PA2_PA2") (pintype "bidirectional"))
    )
    (net (code "169") (name "unconnected-(U$1-PadPA3)") (class "Default")
      (node (ref "U$1") (pin "PA3") (pinfunction "PA3_PA3") (pintype "bidirectional"))
    )
    (net (code "170") (name "unconnected-(U$1-PadPA5)") (class "Default")
      (node (ref "U$1") (pin "PA5") (pinfunction "PA5_PA5") (pintype "bidirectional"))
    )
    (net (code "171") (name "unconnected-(U$1-PadPA7)") (class "Default")
      (node (ref "U$1") (pin "PA7") (pinfunction "PA7_PA7") (pintype "bidirectional"))
    )
    (net (code "172") (name "unconnected-(U$1-PadPA9)") (class "Default")
      (node (ref "U$1") (pin "PA9") (pinfunction "PA9_PA9") (pintype "bidirectional"))
    )
    (net (code "173") (name "unconnected-(U$1-PadPA10)") (class "Default")
      (node (ref "U$1") (pin "PA10") (pinfunction "PA10_PA10") (pintype "bidirectional"))
    )
    (net (code "174") (name "unconnected-(U$1-PadPA11)") (class "Default")
      (node (ref "U$1") (pin "PA11") (pinfunction "PA11_PA11") (pintype "bidirectional"))
    )
    (net (code "175") (name "unconnected-(U$1-PadPA12)") (class "Default")
      (node (ref "U$1") (pin "PA12") (pinfunction "PA12_PA12") (pintype "bidirectional"))
    )
    (net (code "176") (name "unconnected-(U$1-PadPA13)") (class "Default")
      (node (ref "U$1") (pin "PA13") (pinfunction "PA13_PA13") (pintype "bidirectional"))
    )
    (net (code "177") (name "unconnected-(U$1-PadPA14)") (class "Default")
      (node (ref "U$1") (pin "PA14") (pinfunction "PA14_PA14") (pintype "bidirectional"))
    )
    (net (code "178") (name "unconnected-(U$1-PadPB0)") (class "Default")
      (node (ref "U$1") (pin "PB0") (pinfunction "PB0_PB0") (pintype "bidirectional"))
    )
    (net (code "179") (name "unconnected-(U$1-PadPB13)") (class "Default")
      (node (ref "U$1") (pin "PB13") (pinfunction "PB13_PB13") (pintype "bidirectional"))
    )
    (net (code "180") (name "unconnected-(U$1-PadPC1)") (class "Default")
      (node (ref "U$1") (pin "PC1") (pinfunction "PC1_PC1") (pintype "bidirectional"))
    )
    (net (code "181") (name "unconnected-(U$1-PadPC4)") (class "Default")
      (node (ref "U$1") (pin "PC4") (pinfunction "PC4_PC4") (pintype "bidirectional"))
    )
    (net (code "182") (name "unconnected-(U$1-PadPC5)") (class "Default")
      (node (ref "U$1") (pin "PC5") (pinfunction "PC5_PC5") (pintype "bidirectional"))
    )
    (net (code "183") (name "unconnected-(U$1-PadPC13)") (class "Default")
      (node (ref "U$1") (pin "PC13") (pinfunction "PC13_PC13") (pintype "bidirectional"))
    )
    (net (code "184") (name "unconnected-(U$1-PadPC14)") (class "Default")
      (node (ref "U$1") (pin "PC14") (pinfunction "PC14_PC14") (pintype "bidirectional"))
    )
    (net (code "185") (name "unconnected-(U$1-PadPC15)") (class "Default")
      (node (ref "U$1") (pin "PC15") (pinfunction "PC15_PC15") (pintype "bidirectional"))
    )
    (net (code "186") (name "unconnected-(U$1-PadPF0-PH0)") (class "Default")
      (node (ref "U$1") (pin "PF0-PH0") (pinfunction "PF0-PH0_PF0-PH0") (pintype "bidirectional"))
    )
  )
)
